# controller-r3.net
KiCad netlist of a schematic drawn in EAGLE
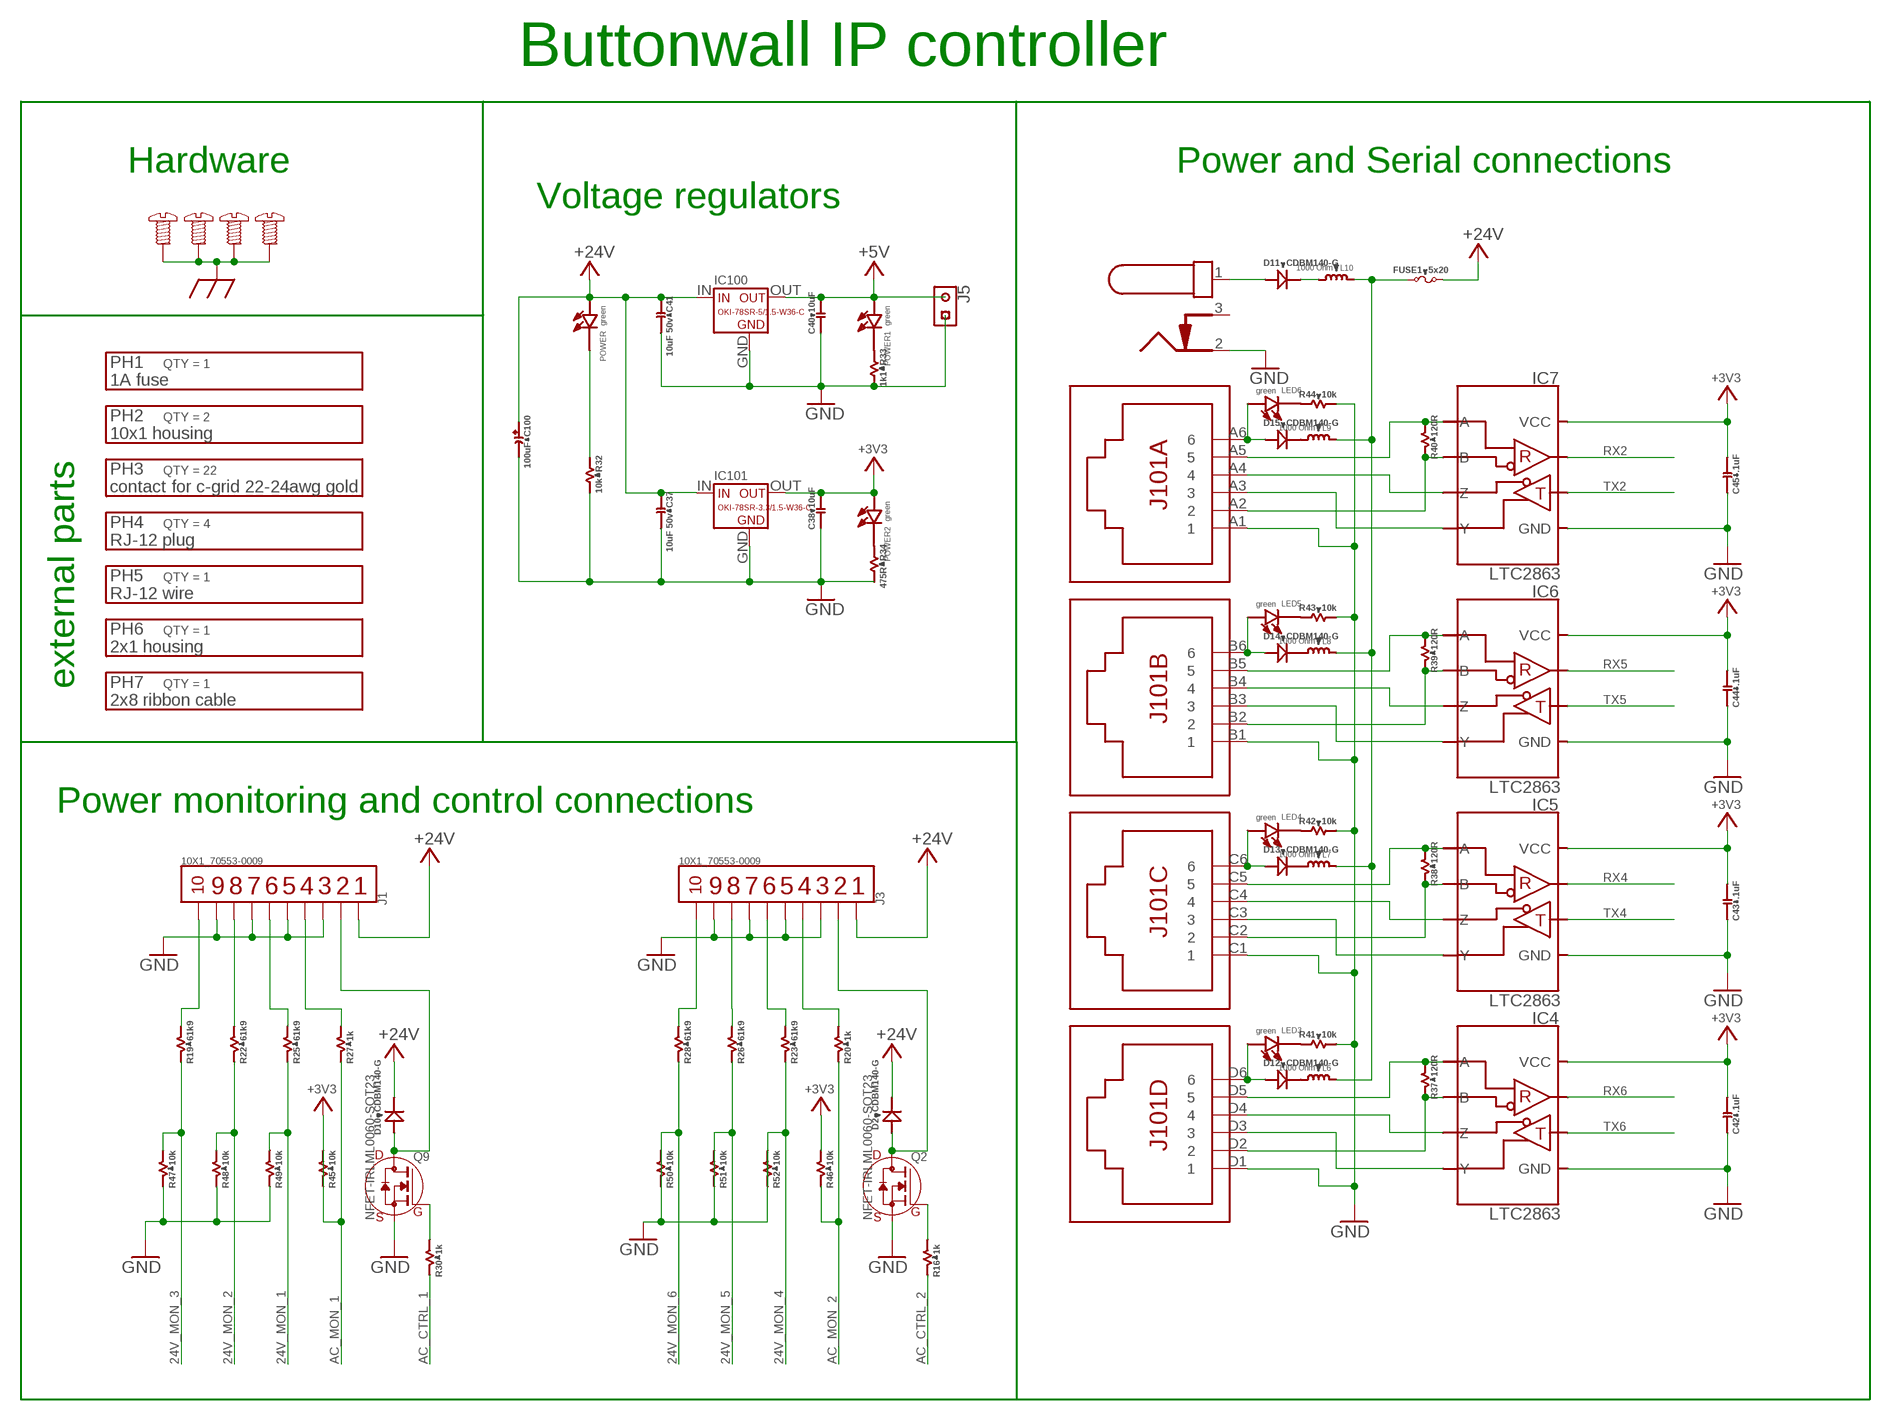
[diagram p0: schematic, sheet 1]
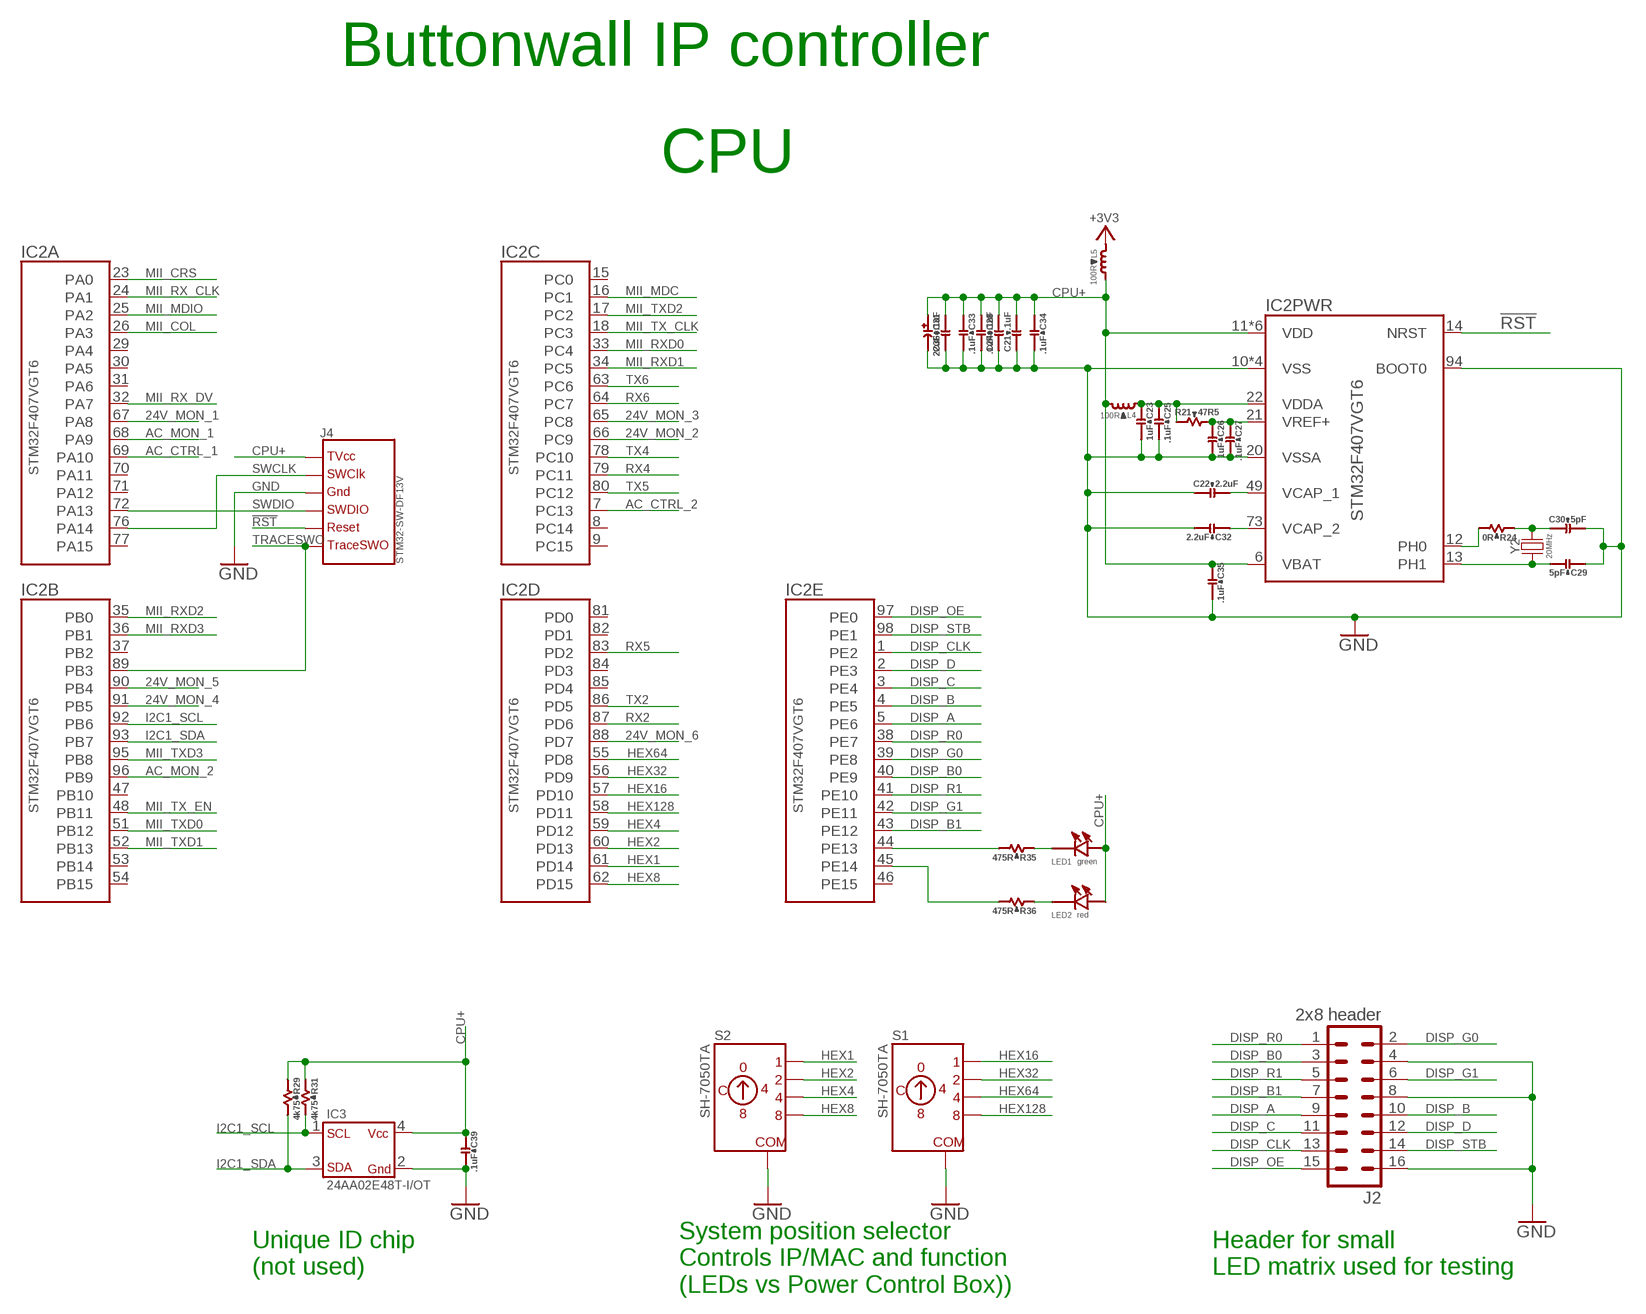
[diagram p1: schematic, sheet 2]
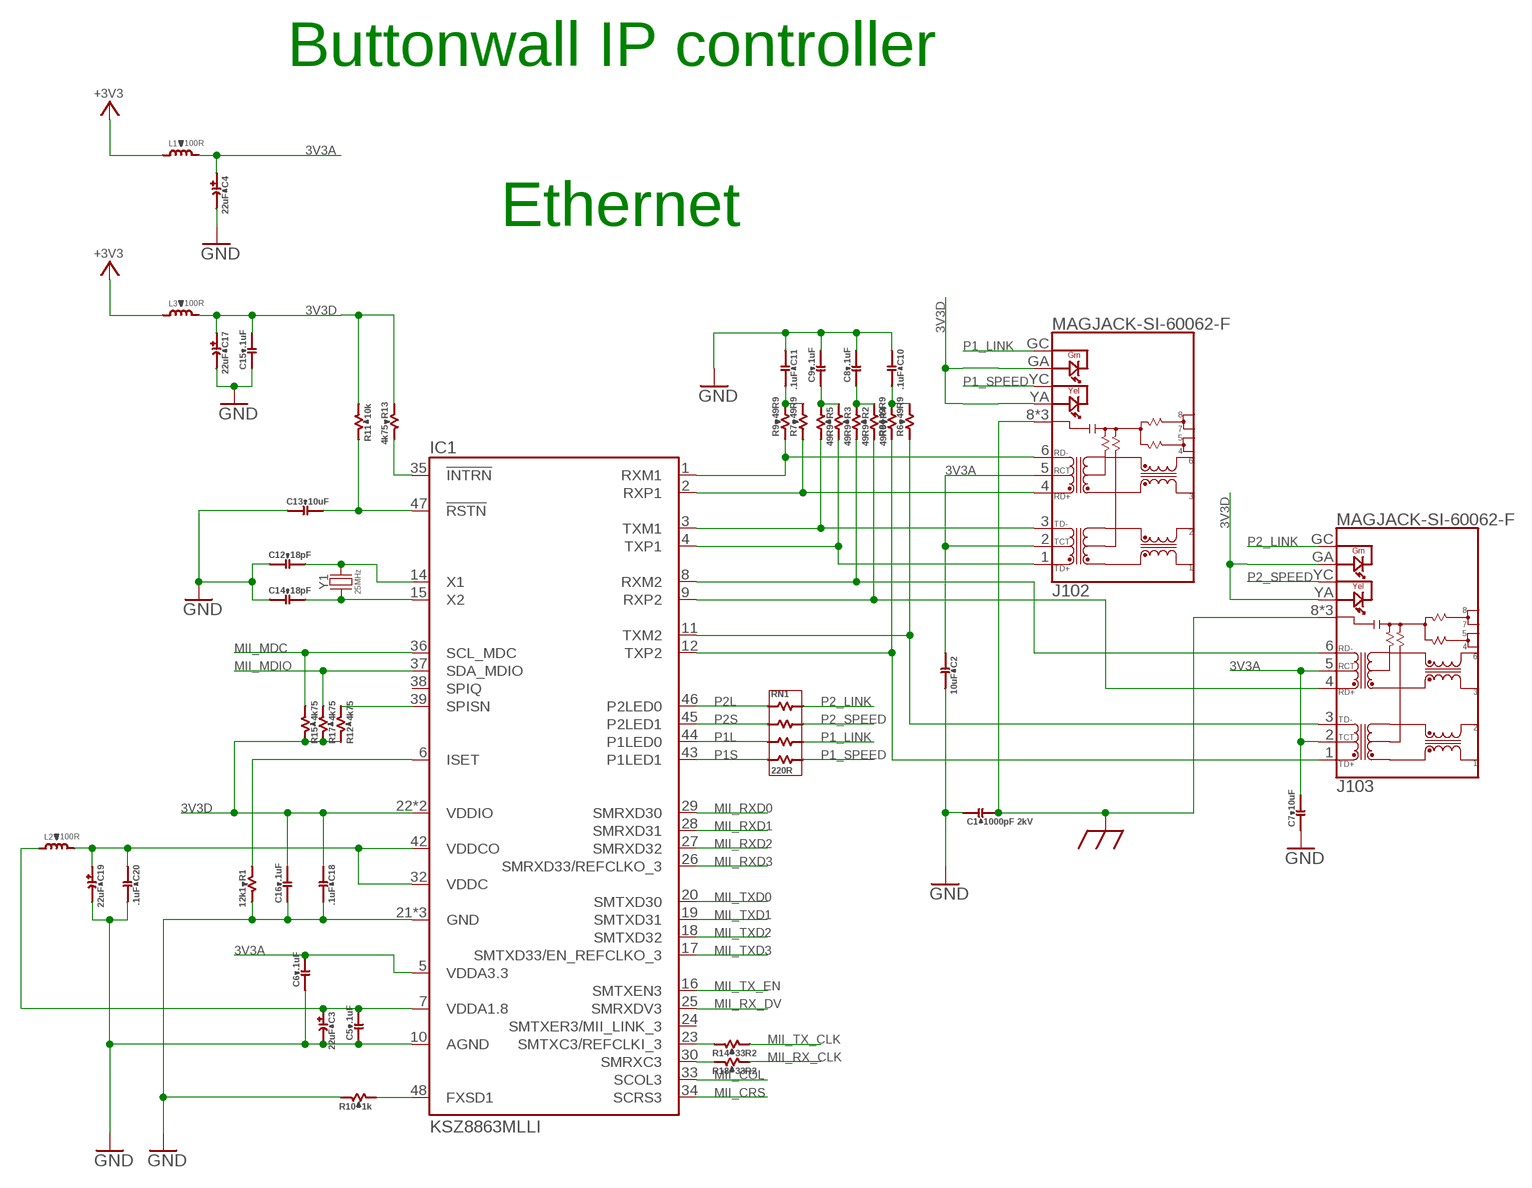
[diagram p2: schematic, sheet 3]

(export (version "E")
  (design (tool "Eeschema 10.0.6"))
  (components
    (comp (ref "C21")
      (value ".1uF")
      (footprint "eagle-import:C0603B")
      (fields (field (name "PARTNO") "CGA3E2X7R1H104K080AA"))
      (libsource (lib "eagle-import") (part "C0603"))
    )
    (comp (ref "C22")
      (value "2.2uF")
      (footprint "eagle-import:C0603B")
      (fields (field (name "PARTNO") "C1608X5R1V225K080AC"))
      (libsource (lib "eagle-import") (part "C0603"))
    )
    (comp (ref "C23")
      (value "1uF")
      (footprint "eagle-import:C0603B")
      (fields (field (name "PARTNO") "CGA3E3X5R1H105K080AB"))
      (libsource (lib "eagle-import") (part "C0603"))
    )
    (comp (ref "C24")
      (value ".1uF")
      (footprint "eagle-import:C0603B")
      (fields (field (name "PARTNO") "CGA3E2X7R1H104K080AA"))
      (libsource (lib "eagle-import") (part "C0603"))
    )
    (comp (ref "C25")
      (value ".1uF")
      (footprint "eagle-import:C0603B")
      (fields (field (name "PARTNO") "CGA3E2X7R1H104K080AA"))
      (libsource (lib "eagle-import") (part "C0603"))
    )
    (comp (ref "C26")
      (value "1uF")
      (footprint "eagle-import:C0603B")
      (fields (field (name "PARTNO") "CGA3E3X5R1H105K080AB"))
      (libsource (lib "eagle-import") (part "C0603"))
    )
    (comp (ref "C27")
      (value ".1uF")
      (footprint "eagle-import:C0603B")
      (fields (field (name "PARTNO") "CGA3E2X7R1H104K080AA"))
      (libsource (lib "eagle-import") (part "C0603"))
    )
    (comp (ref "C28")
      (value ".1uF")
      (footprint "eagle-import:C0603B")
      (fields (field (name "PARTNO") "CGA3E2X7R1H104K080AA"))
      (libsource (lib "eagle-import") (part "C0603"))
    )
    (comp (ref "C29")
      (value "5pF")
      (footprint "eagle-import:C0603B")
      (fields (field (name "PARTNO") "CGA3E2C0G1H050C080AA"))
      (libsource (lib "eagle-import") (part "C0603"))
    )
    (comp (ref "C30")
      (value "5pF")
      (footprint "eagle-import:C0603B")
      (fields (field (name "PARTNO") "CGA3E2C0G1H050C080AA"))
      (libsource (lib "eagle-import") (part "C0603"))
    )
    (comp (ref "C31")
      (value "22uF")
      (footprint "eagle-import:B_3528-21R")
      (fields (field (name "PARTNO") "293D226X96R3B2TE3"))
      (libsource (lib "eagle-import") (part "CPOL-B/3528"))
    )
    (comp (ref "C32")
      (value "2.2uF")
      (footprint "eagle-import:C0603B")
      (fields (field (name "PARTNO") "C1608X5R1V225K080AC"))
      (libsource (lib "eagle-import") (part "C0603"))
    )
    (comp (ref "C33")
      (value ".1uF")
      (footprint "eagle-import:C0603B")
      (fields (field (name "PARTNO") "CGA3E2X7R1H104K080AA"))
      (libsource (lib "eagle-import") (part "C0603"))
    )
    (comp (ref "C34")
      (value ".1uF")
      (footprint "eagle-import:C0603B")
      (fields (field (name "PARTNO") "CGA3E2X7R1H104K080AA"))
      (libsource (lib "eagle-import") (part "C0603"))
    )
    (comp (ref "C35")
      (value ".1uF")
      (footprint "eagle-import:C0603B")
      (fields (field (name "PARTNO") "CGA3E2X7R1H104K080AA"))
      (libsource (lib "eagle-import") (part "C0603"))
    )
    (comp (ref "C36")
      (value ".1uF")
      (footprint "eagle-import:C0603B")
      (fields (field (name "PARTNO") "CGA3E2X7R1H104K080AA"))
      (libsource (lib "eagle-import") (part "C0603"))
    )
    (comp (ref "C39")
      (value ".1uF")
      (footprint "eagle-import:C0603B")
      (fields (field (name "PARTNO") "CGA3E2X7R1H104K080AA"))
      (libsource (lib "eagle-import") (part "C0603"))
    )
    (comp (ref "IC2")
      (value "STM32F407VGT6")
      (footprint "eagle-import:LQFP-100")
      (fields (field (name "PARTNO") "STM32F407VGT6"))
      (libsource (lib "eagle-import") (part "STM32F40V_T7"))
    )
    (comp (ref "IC3")
      (value "24AA02E48T-I/OT")
      (footprint "eagle-import:SOT-23-5")
      (libsource (lib "eagle-import") (part "24AA02E48T-I/OT"))
    )
    (comp (ref "J2")
      (value "2x8 header")
      (footprint "eagle-import:ML16")
      (fields (field (name "PARTNO") "SBH11-PBPC-D08-ST-BK"))
      (libsource (lib "eagle-import") (part "ML16"))
    )
    (comp (ref "J4")
      (value "STM32-SW-DF13V")
      (footprint "eagle-import:DF13-6P-1.25V")
      (fields (field (name "PARTNO") "DF13C-6P-1.25V(20)"))
      (libsource (lib "eagle-import") (part "STM32-SW-DF13V"))
    )
    (comp (ref "L4")
      (value "100R")
      (footprint "eagle-import:R0603B")
      (fields (field (name "PARTNO") "MPZ1608S101A"))
      (libsource (lib "eagle-import") (part "L0603"))
    )
    (comp (ref "L5")
      (value "100R")
      (footprint "eagle-import:R0603B")
      (fields (field (name "PARTNO") "MPZ1608S101A"))
      (libsource (lib "eagle-import") (part "L0603"))
    )
    (comp (ref "LED1")
      (value "green")
      (footprint "eagle-import:CHIPLED_0603")
      (fields (field (name "PARTNO") "LTST-C190KGKT"))
      (libsource (lib "eagle-import") (part "LED0603"))
    )
    (comp (ref "LED2")
      (value "red")
      (footprint "eagle-import:CHIPLED_0603")
      (fields (field (name "PARTNO") "LTST-C190KRKT"))
      (libsource (lib "eagle-import") (part "LED0603"))
    )
    (comp (ref "R21")
      (value "47R5")
      (footprint "eagle-import:R0603B")
      (fields (field (name "PARTNO") "CRCW060347R5FKEA"))
      (libsource (lib "eagle-import") (part "R0603"))
    )
    (comp (ref "R24")
      (value "0R")
      (footprint "eagle-import:R0603B")
      (fields (field (name "PARTNO") "CRCW06030000Z0EA"))
      (libsource (lib "eagle-import") (part "R0603"))
    )
    (comp (ref "R29")
      (value "4k75")
      (footprint "eagle-import:R0603B")
      (fields (field (name "PARTNO") "CRCW06034K75FKEA"))
      (libsource (lib "eagle-import") (part "R0603"))
    )
    (comp (ref "R31")
      (value "4k75")
      (footprint "eagle-import:R0603B")
      (fields (field (name "PARTNO") "CRCW06034K75FKEA"))
      (libsource (lib "eagle-import") (part "R0603"))
    )
    (comp (ref "R35")
      (value "475R")
      (footprint "eagle-import:R0603B")
      (fields (field (name "PARTNO") "CRCW0603475RFKEA"))
      (libsource (lib "eagle-import") (part "R0603"))
    )
    (comp (ref "R36")
      (value "475R")
      (footprint "eagle-import:R0603B")
      (fields (field (name "PARTNO") "CRCW0603475RFKEA"))
      (libsource (lib "eagle-import") (part "R0603"))
    )
    (comp (ref "S1")
      (value "SH-7050TA")
      (footprint "eagle-import:SH-7050TA")
      (libsource (lib "eagle-import") (part "HEXROTARY"))
    )
    (comp (ref "S2")
      (value "SH-7050TA")
      (footprint "eagle-import:SH-7050TA")
      (libsource (lib "eagle-import") (part "HEXROTARY"))
    )
    (comp (ref "Y2")
      (value "20MHz")
      (footprint "eagle-import:5X3.2")
      (fields (field (name "PARTNO") "7A-20.000MAHE-T"))
      (libsource (lib "eagle-import") (part "XTAL-2_5X3.2"))
    )
    (comp (ref "C37")
      (value "10uF 50v")
      (footprint "eagle-import:C1206B")
      (fields (field (name "PARTNO") "CL31A106KBHNNNE"))
      (libsource (lib "eagle-import") (part "C1206"))
    )
    (comp (ref "C38")
      (value "10uF")
      (footprint "eagle-import:C0603B")
      (fields (field (name "PARTNO") "C1608X6S1A106M080AC"))
      (libsource (lib "eagle-import") (part "C0603"))
    )
    (comp (ref "C40")
      (value "10uF")
      (footprint "eagle-import:C0603B")
      (fields (field (name "PARTNO") "C1608X6S1A106M080AC"))
      (libsource (lib "eagle-import") (part "C0603"))
    )
    (comp (ref "C41")
      (value "10uF 50v")
      (footprint "eagle-import:C1206B")
      (fields (field (name "PARTNO") "CL31A106KBHNNNE"))
      (libsource (lib "eagle-import") (part "C1206"))
    )
    (comp (ref "C42")
      (value ".1uF")
      (footprint "eagle-import:C0603B")
      (fields (field (name "PARTNO") "CGA3E2X7R1H104K080AA"))
      (libsource (lib "eagle-import") (part "C0603"))
    )
    (comp (ref "C43")
      (value ".1uF")
      (footprint "eagle-import:C0603B")
      (fields (field (name "PARTNO") "CGA3E2X7R1H104K080AA"))
      (libsource (lib "eagle-import") (part "C0603"))
    )
    (comp (ref "C44")
      (value ".1uF")
      (footprint "eagle-import:C0603B")
      (fields (field (name "PARTNO") "CGA3E2X7R1H104K080AA"))
      (libsource (lib "eagle-import") (part "C0603"))
    )
    (comp (ref "C45")
      (value ".1uF")
      (footprint "eagle-import:C0603B")
      (fields (field (name "PARTNO") "CGA3E2X7R1H104K080AA"))
      (libsource (lib "eagle-import") (part "C0603"))
    )
    (comp (ref "C100")
      (value "100uF")
      (footprint "eagle-import:E3,5-8")
      (fields (field (name "PARTNO") "EEU-FM1H101"))
      (libsource (lib "eagle-import") (part "CPOL-TH-3.5-8"))
    )
    (comp (ref "D2")
      (value "CDBM140-G")
      (footprint "eagle-import:SOD-123")
      (libsource (lib "eagle-import") (part "D_SOD123"))
    )
    (comp (ref "D10")
      (value "CDBM140-G")
      (footprint "eagle-import:SOD-123")
      (libsource (lib "eagle-import") (part "D_SOD123"))
    )
    (comp (ref "D11")
      (value "CDBM140-G")
      (footprint "eagle-import:SOD-123")
      (libsource (lib "eagle-import") (part "D_SOD123"))
    )
    (comp (ref "D12")
      (value "CDBM140-G")
      (footprint "eagle-import:SOD-123")
      (libsource (lib "eagle-import") (part "D_SOD123"))
    )
    (comp (ref "D13")
      (value "CDBM140-G")
      (footprint "eagle-import:SOD-123")
      (libsource (lib "eagle-import") (part "D_SOD123"))
    )
    (comp (ref "D14")
      (value "CDBM140-G")
      (footprint "eagle-import:SOD-123")
      (libsource (lib "eagle-import") (part "D_SOD123"))
    )
    (comp (ref "D15")
      (value "CDBM140-G")
      (footprint "eagle-import:SOD-123")
      (libsource (lib "eagle-import") (part "D_SOD123"))
    )
    (comp (ref "FUSE1")
      (value "5x20")
      (footprint "eagle-import:649")
      (fields (field (name "PARTNO") "64900001039"))
      (libsource (lib "eagle-import") (part "F-649"))
    )
    (comp (ref "IC4")
      (value "LTC2863")
      (footprint "eagle-import:SO08")
      (fields (field (name "PARTNO") "LTC2863IS8-1#PBF"))
      (libsource (lib "eagle-import") (part "LTC2863"))
    )
    (comp (ref "IC5")
      (value "LTC2863")
      (footprint "eagle-import:SO08")
      (fields (field (name "PARTNO") "LTC2863IS8-1#PBF"))
      (libsource (lib "eagle-import") (part "LTC2863"))
    )
    (comp (ref "IC6")
      (value "LTC2863")
      (footprint "eagle-import:SO08")
      (fields (field (name "PARTNO") "LTC2863IS8-1#PBF"))
      (libsource (lib "eagle-import") (part "LTC2863"))
    )
    (comp (ref "IC7")
      (value "LTC2863")
      (footprint "eagle-import:SO08")
      (fields (field (name "PARTNO") "LTC2863IS8-1#PBF"))
      (libsource (lib "eagle-import") (part "LTC2863"))
    )
    (comp (ref "IC100")
      (value "OKI-78SR-5/1.5-W36-C")
      (footprint "eagle-import:OKI-78SR-V")
      (libsource (lib "eagle-import") (part "OKI-78SR--W36-C5/1.5"))
    )
    (comp (ref "IC101")
      (value "OKI-78SR-3.3/1.5-W36-C")
      (footprint "eagle-import:OKI-78SR-V")
      (libsource (lib "eagle-import") (part "OKI-78SR--W36-C3.3/1.5"))
    )
    (comp (ref "J1")
      (value "10X1_70553-0009")
      (footprint "eagle-import:MOLEX_70553-(10)")
      (fields (field (name "PARTNO") "0705530009"))
      (libsource (lib "eagle-import") (part "10X1_70553-0009"))
    )
    (comp (ref "J3")
      (value "10X1_70553-0009")
      (footprint "eagle-import:MOLEX_70553-(10)")
      (fields (field (name "PARTNO") "0705530009"))
      (libsource (lib "eagle-import") (part "10X1_70553-0009"))
    )
    (comp (ref "J5")
      (value "1X2_70543")
      (footprint "eagle-import:MOLEX_70543-0001")
      (fields (field (name "PARTNO") "0705430001"))
      (libsource (lib "eagle-import") (part "1X2_70543"))
    )
    (comp (ref "J100")
      (value "PJ-102AH")
      (footprint "eagle-import:PJ-102(DC_JACK)")
      (libsource (lib "eagle-import") (part "DC_JACK"))
    )
    (comp (ref "J101")
      (value "RJ12-QUAD")
      (footprint "eagle-import:SS-666604-NF")
      (fields (field (name "PARTNO") "SS-666604-NF"))
      (libsource (lib "eagle-import") (part "RJ12-QUAD"))
    )
    (comp (ref "L6")
      (value "1000 Ohm")
      (footprint "eagle-import:R0603B")
      (fields (field (name "PARTNO") "MMZ1608R102A"))
      (libsource (lib "eagle-import") (part "L0603"))
    )
    (comp (ref "L7")
      (value "1000 Ohm")
      (footprint "eagle-import:R0603B")
      (fields (field (name "PARTNO") "MMZ1608R102A"))
      (libsource (lib "eagle-import") (part "L0603"))
    )
    (comp (ref "L8")
      (value "1000 Ohm")
      (footprint "eagle-import:R0603B")
      (fields (field (name "PARTNO") "MMZ1608R102A"))
      (libsource (lib "eagle-import") (part "L0603"))
    )
    (comp (ref "L9")
      (value "1000 Ohm")
      (footprint "eagle-import:R0603B")
      (fields (field (name "PARTNO") "MMZ1608R102A"))
      (libsource (lib "eagle-import") (part "L0603"))
    )
    (comp (ref "L10")
      (value "1000 Ohm")
      (footprint "eagle-import:R0603B")
      (fields (field (name "PARTNO") "MMZ1608R102A"))
      (libsource (lib "eagle-import") (part "L0603"))
    )
    (comp (ref "LED3")
      (value "green")
      (footprint "eagle-import:CHIPLED_0603")
      (fields (field (name "PARTNO") "LTST-C190KGKT"))
      (libsource (lib "eagle-import") (part "LED0603"))
    )
    (comp (ref "LED4")
      (value "green")
      (footprint "eagle-import:CHIPLED_0603")
      (fields (field (name "PARTNO") "LTST-C190KGKT"))
      (libsource (lib "eagle-import") (part "LED0603"))
    )
    (comp (ref "LED5")
      (value "green")
      (footprint "eagle-import:CHIPLED_0603")
      (fields (field (name "PARTNO") "LTST-C190KGKT"))
      (libsource (lib "eagle-import") (part "LED0603"))
    )
    (comp (ref "LED6")
      (value "green")
      (footprint "eagle-import:CHIPLED_0603")
      (fields (field (name "PARTNO") "LTST-C190KGKT"))
      (libsource (lib "eagle-import") (part "LED0603"))
    )
    (comp (ref "POWER")
      (value "green")
      (footprint "eagle-import:CHIPLED_0603")
      (fields (field (name "PARTNO") "LTST-C190KGKT"))
      (libsource (lib "eagle-import") (part "LED0603"))
    )
    (comp (ref "POWER1")
      (value "green")
      (footprint "eagle-import:CHIPLED_0603")
      (fields (field (name "PARTNO") "LTST-C190KGKT"))
      (libsource (lib "eagle-import") (part "LED0603"))
    )
    (comp (ref "POWER2")
      (value "green")
      (footprint "eagle-import:CHIPLED_0603")
      (fields (field (name "PARTNO") "LTST-C190KGKT"))
      (libsource (lib "eagle-import") (part "LED0603"))
    )
    (comp (ref "Q2")
      (value "NFET-IRLML0060-SOT23")
      (footprint "eagle-import:SOT-23")
      (fields (field (name "PARTNO") "IRLML0060TRPBF"))
      (libsource (lib "eagle-import") (part "NFET--SOT23IRLML0060"))
    )
    (comp (ref "Q9")
      (value "NFET-IRLML0060-SOT23")
      (footprint "eagle-import:SOT-23")
      (fields (field (name "PARTNO") "IRLML0060TRPBF"))
      (libsource (lib "eagle-import") (part "NFET--SOT23IRLML0060"))
    )
    (comp (ref "R16")
      (value "1k")
      (footprint "eagle-import:R0603B")
      (fields (field (name "PARTNO") "CRCW06031K00FKEA"))
      (libsource (lib "eagle-import") (part "R0603"))
    )
    (comp (ref "R19")
      (value "61k9")
      (footprint "eagle-import:R0603B")
      (fields (field (name "PARTNO") "CRCW060361K9FKEA"))
      (libsource (lib "eagle-import") (part "R0603"))
    )
    (comp (ref "R20")
      (value "1k")
      (footprint "eagle-import:R0603B")
      (fields (field (name "PARTNO") "CRCW06031K00FKEA"))
      (libsource (lib "eagle-import") (part "R0603"))
    )
    (comp (ref "R22")
      (value "61k9")
      (footprint "eagle-import:R0603B")
      (fields (field (name "PARTNO") "CRCW060361K9FKEA"))
      (libsource (lib "eagle-import") (part "R0603"))
    )
    (comp (ref "R23")
      (value "61k9")
      (footprint "eagle-import:R0603B")
      (fields (field (name "PARTNO") "CRCW060361K9FKEA"))
      (libsource (lib "eagle-import") (part "R0603"))
    )
    (comp (ref "R25")
      (value "61k9")
      (footprint "eagle-import:R0603B")
      (fields (field (name "PARTNO") "CRCW060361K9FKEA"))
      (libsource (lib "eagle-import") (part "R0603"))
    )
    (comp (ref "R26")
      (value "61k9")
      (footprint "eagle-import:R0603B")
      (fields (field (name "PARTNO") "CRCW060361K9FKEA"))
      (libsource (lib "eagle-import") (part "R0603"))
    )
    (comp (ref "R27")
      (value "1k")
      (footprint "eagle-import:R0603B")
      (fields (field (name "PARTNO") "CRCW06031K00FKEA"))
      (libsource (lib "eagle-import") (part "R0603"))
    )
    (comp (ref "R28")
      (value "61k9")
      (footprint "eagle-import:R0603B")
      (fields (field (name "PARTNO") "CRCW060361K9FKEA"))
      (libsource (lib "eagle-import") (part "R0603"))
    )
    (comp (ref "R30")
      (value "1k")
      (footprint "eagle-import:R0603B")
      (fields (field (name "PARTNO") "CRCW06031K00FKEA"))
      (libsource (lib "eagle-import") (part "R0603"))
    )
    (comp (ref "R32")
      (value "10k")
      (footprint "eagle-import:R0603B")
      (fields (field (name "PARTNO") "CRCW060310K0FKEA"))
      (libsource (lib "eagle-import") (part "R0603"))
    )
    (comp (ref "R33")
      (value "1k1")
      (footprint "eagle-import:R0603B")
      (fields (field (name "PARTNO") "CRCW06031K10FKEA"))
      (libsource (lib "eagle-import") (part "R0603"))
    )
    (comp (ref "R34")
      (value "475R")
      (footprint "eagle-import:R0603B")
      (fields (field (name "PARTNO") "CRCW0603475RFKEA"))
      (libsource (lib "eagle-import") (part "R0603"))
    )
    (comp (ref "R37")
      (value "120R")
      (footprint "eagle-import:R1206B")
      (fields (field (name "PARTNO") "CRCW1206120RFKEA"))
      (libsource (lib "eagle-import") (part "R1206"))
    )
    (comp (ref "R38")
      (value "120R")
      (footprint "eagle-import:R1206B")
      (fields (field (name "PARTNO") "CRCW1206120RFKEA"))
      (libsource (lib "eagle-import") (part "R1206"))
    )
    (comp (ref "R39")
      (value "120R")
      (footprint "eagle-import:R1206B")
      (fields (field (name "PARTNO") "CRCW1206120RFKEA"))
      (libsource (lib "eagle-import") (part "R1206"))
    )
    (comp (ref "R40")
      (value "120R")
      (footprint "eagle-import:R1206B")
      (fields (field (name "PARTNO") "CRCW1206120RFKEA"))
      (libsource (lib "eagle-import") (part "R1206"))
    )
    (comp (ref "R41")
      (value "10k")
      (footprint "eagle-import:R0603B")
      (fields (field (name "PARTNO") "CRCW060310K0FKEA"))
      (libsource (lib "eagle-import") (part "R0603"))
    )
    (comp (ref "R42")
      (value "10k")
      (footprint "eagle-import:R0603B")
      (fields (field (name "PARTNO") "CRCW060310K0FKEA"))
      (libsource (lib "eagle-import") (part "R0603"))
    )
    (comp (ref "R43")
      (value "10k")
      (footprint "eagle-import:R0603B")
      (fields (field (name "PARTNO") "CRCW060310K0FKEA"))
      (libsource (lib "eagle-import") (part "R0603"))
    )
    (comp (ref "R44")
      (value "10k")
      (footprint "eagle-import:R0603B")
      (fields (field (name "PARTNO") "CRCW060310K0FKEA"))
      (libsource (lib "eagle-import") (part "R0603"))
    )
    (comp (ref "R45")
      (value "10k")
      (footprint "eagle-import:R0603B")
      (fields (field (name "PARTNO") "CRCW060310K0FKEA"))
      (libsource (lib "eagle-import") (part "R0603"))
    )
    (comp (ref "R46")
      (value "10k")
      (footprint "eagle-import:R0603B")
      (fields (field (name "PARTNO") "CRCW060310K0FKEA"))
      (libsource (lib "eagle-import") (part "R0603"))
    )
    (comp (ref "R47")
      (value "10k")
      (footprint "eagle-import:R0603B")
      (fields (field (name "PARTNO") "CRCW060310K0FKEA"))
      (libsource (lib "eagle-import") (part "R0603"))
    )
    (comp (ref "R48")
      (value "10k")
      (footprint "eagle-import:R0603B")
      (fields (field (name "PARTNO") "CRCW060310K0FKEA"))
      (libsource (lib "eagle-import") (part "R0603"))
    )
    (comp (ref "R49")
      (value "10k")
      (footprint "eagle-import:R0603B")
      (fields (field (name "PARTNO") "CRCW060310K0FKEA"))
      (libsource (lib "eagle-import") (part "R0603"))
    )
    (comp (ref "R50")
      (value "10k")
      (footprint "eagle-import:R0603B")
      (fields (field (name "PARTNO") "CRCW060310K0FKEA"))
      (libsource (lib "eagle-import") (part "R0603"))
    )
    (comp (ref "R51")
      (value "10k")
      (footprint "eagle-import:R0603B")
      (fields (field (name "PARTNO") "CRCW060310K0FKEA"))
      (libsource (lib "eagle-import") (part "R0603"))
    )
    (comp (ref "R52")
      (value "10k")
      (footprint "eagle-import:R0603B")
      (fields (field (name "PARTNO") "CRCW060310K0FKEA"))
      (libsource (lib "eagle-import") (part "R0603"))
    )
    (comp (ref "SCREW1")
      (value "SCREW-632-0-PSHP")
      (footprint "eagle-import:SMTPR-6-1")
      (libsource (lib "eagle-import") (part "SCREW--PSHP632-0"))
    )
    (comp (ref "SCREW2")
      (value "SCREW-632-0-PSHP")
      (footprint "eagle-import:SMTPR-6-1")
      (libsource (lib "eagle-import") (part "SCREW--PSHP632-0"))
    )
    (comp (ref "SCREW3")
      (value "SCREW-632-0-PSHP")
      (footprint "eagle-import:SMTPR-6-1")
      (libsource (lib "eagle-import") (part "SCREW--PSHP632-0"))
    )
    (comp (ref "SCREW4")
      (value "SCREW-632-0-PSHP")
      (footprint "eagle-import:SMTPR-6-1")
      (libsource (lib "eagle-import") (part "SCREW--PSHP632-0"))
    )
    (comp (ref "C1")
      (value "1000pF 2kV")
      (footprint "eagle-import:C1206B")
      (fields (field (name "PARTNO") "202R18W102KV4E"))
      (libsource (lib "eagle-import") (part "C1206"))
    )
    (comp (ref "C2")
      (value "10uF")
      (footprint "eagle-import:C0603B")
      (fields (field (name "PARTNO") "C1608X6S1A106M080AC"))
      (libsource (lib "eagle-import") (part "C0603"))
    )
    (comp (ref "C3")
      (value "22uF")
      (footprint "eagle-import:B_3528-21R")
      (fields (field (name "PARTNO") "293D226X96R3B2TE3"))
      (libsource (lib "eagle-import") (part "CPOL-B/3528"))
    )
    (comp (ref "C4")
      (value "22uF")
      (footprint "eagle-import:B_3528-21R")
      (fields (field (name "PARTNO") "293D226X96R3B2TE3"))
      (libsource (lib "eagle-import") (part "CPOL-B/3528"))
    )
    (comp (ref "C5")
      (value ".1uF")
      (footprint "eagle-import:C0603B")
      (fields (field (name "PARTNO") "CGA3E2X7R1H104K080AA"))
      (libsource (lib "eagle-import") (part "C0603"))
    )
    (comp (ref "C6")
      (value ".1uF")
      (footprint "eagle-import:C0603B")
      (fields (field (name "PARTNO") "CGA3E2X7R1H104K080AA"))
      (libsource (lib "eagle-import") (part "C0603"))
    )
    (comp (ref "C7")
      (value "10uF")
      (footprint "eagle-import:C0603B")
      (fields (field (name "PARTNO") "C1608X6S1A106M080AC"))
      (libsource (lib "eagle-import") (part "C0603"))
    )
    (comp (ref "C8")
      (value ".1uF")
      (footprint "eagle-import:C0603B")
      (fields (field (name "PARTNO") "CGA3E2X7R1H104K080AA"))
      (libsource (lib "eagle-import") (part "C0603"))
    )
    (comp (ref "C9")
      (value ".1uF")
      (footprint "eagle-import:C0603B")
      (fields (field (name "PARTNO") "CGA3E2X7R1H104K080AA"))
      (libsource (lib "eagle-import") (part "C0603"))
    )
    (comp (ref "C10")
      (value ".1uF")
      (footprint "eagle-import:C0603B")
      (fields (field (name "PARTNO") "CGA3E2X7R1H104K080AA"))
      (libsource (lib "eagle-import") (part "C0603"))
    )
    (comp (ref "C11")
      (value ".1uF")
      (footprint "eagle-import:C0603B")
      (fields (field (name "PARTNO") "CGA3E2X7R1H104K080AA"))
      (libsource (lib "eagle-import") (part "C0603"))
    )
    (comp (ref "C12")
      (value "18pF")
      (footprint "eagle-import:C0603B")
      (fields (field (name "PARTNO") "CGA3E2C0G1H180J080AA"))
      (libsource (lib "eagle-import") (part "C0603"))
    )
    (comp (ref "C13")
      (value "10uF")
      (footprint "eagle-import:C0603B")
      (fields (field (name "PARTNO") "C1608X6S1A106M080AC"))
      (libsource (lib "eagle-import") (part "C0603"))
    )
    (comp (ref "C14")
      (value "18pF")
      (footprint "eagle-import:C0603B")
      (fields (field (name "PARTNO") "CGA3E2C0G1H180J080AA"))
      (libsource (lib "eagle-import") (part "C0603"))
    )
    (comp (ref "C15")
      (value ".1uF")
      (footprint "eagle-import:C0603B")
      (fields (field (name "PARTNO") "CGA3E2X7R1H104K080AA"))
      (libsource (lib "eagle-import") (part "C0603"))
    )
    (comp (ref "C16")
      (value ".1uF")
      (footprint "eagle-import:C0603B")
      (fields (field (name "PARTNO") "CGA3E2X7R1H104K080AA"))
      (libsource (lib "eagle-import") (part "C0603"))
    )
    (comp (ref "C17")
      (value "22uF")
      (footprint "eagle-import:B_3528-21R")
      (fields (field (name "PARTNO") "293D226X96R3B2TE3"))
      (libsource (lib "eagle-import") (part "CPOL-B/3528"))
    )
    (comp (ref "C18")
      (value ".1uF")
      (footprint "eagle-import:C0603B")
      (fields (field (name "PARTNO") "CGA3E2X7R1H104K080AA"))
      (libsource (lib "eagle-import") (part "C0603"))
    )
    (comp (ref "C19")
      (value "22uF")
      (footprint "eagle-import:B_3528-21R")
      (fields (field (name "PARTNO") "293D226X96R3B2TE3"))
      (libsource (lib "eagle-import") (part "CPOL-B/3528"))
    )
    (comp (ref "C20")
      (value ".1uF")
      (footprint "eagle-import:C0603B")
      (fields (field (name "PARTNO") "CGA3E2X7R1H104K080AA"))
      (libsource (lib "eagle-import") (part "C0603"))
    )
    (comp (ref "IC1")
      (value "KSZ8863MLLI")
      (footprint "eagle-import:TQFP48")
      (libsource (lib "eagle-import") (part "KSZ8863MLLI"))
    )
    (comp (ref "J102")
      (value "MAGJACK-SI-60062-F")
      (footprint "eagle-import:SI-60062-F")
      (fields (field (name "PARTNO") "SI-60062-F"))
      (libsource (lib "eagle-import") (part "MAGJACK-SI-60062-F"))
    )
    (comp (ref "J103")
      (value "MAGJACK-SI-60062-F")
      (footprint "eagle-import:SI-60062-F")
      (fields (field (name "PARTNO") "SI-60062-F"))
      (libsource (lib "eagle-import") (part "MAGJACK-SI-60062-F"))
    )
    (comp (ref "L1")
      (value "100R")
      (footprint "eagle-import:R0603B")
      (fields (field (name "PARTNO") "MPZ1608S101A"))
      (libsource (lib "eagle-import") (part "L0603"))
    )
    (comp (ref "L2")
      (value "100R")
      (footprint "eagle-import:R0603B")
      (fields (field (name "PARTNO") "MPZ1608S101A"))
      (libsource (lib "eagle-import") (part "L0603"))
    )
    (comp (ref "L3")
      (value "100R")
      (footprint "eagle-import:R0603B")
      (fields (field (name "PARTNO") "MPZ1608S101A"))
      (libsource (lib "eagle-import") (part "L0603"))
    )
    (comp (ref "R1")
      (value "12k1")
      (footprint "eagle-import:R0603B")
      (fields (field (name "PARTNO") "CRCW060312K1FKEA"))
      (libsource (lib "eagle-import") (part "R0603"))
    )
    (comp (ref "R2")
      (value "49R9")
      (footprint "eagle-import:R0603B")
      (fields (field (name "PARTNO") "CRCW060349R9FKEA"))
      (libsource (lib "eagle-import") (part "R0603"))
    )
    (comp (ref "R3")
      (value "49R9")
      (footprint "eagle-import:R0603B")
      (fields (field (name "PARTNO") "CRCW060349R9FKEA"))
      (libsource (lib "eagle-import") (part "R0603"))
    )
    (comp (ref "R4")
      (value "49R9")
      (footprint "eagle-import:R0603B")
      (fields (field (name "PARTNO") "CRCW060349R9FKEA"))
      (libsource (lib "eagle-import") (part "R0603"))
    )
    (comp (ref "R5")
      (value "49R9")
      (footprint "eagle-import:R0603B")
      (fields (field (name "PARTNO") "CRCW060349R9FKEA"))
      (libsource (lib "eagle-import") (part "R0603"))
    )
    (comp (ref "R6")
      (value "49R9")
      (footprint "eagle-import:R0603B")
      (fields (field (name "PARTNO") "CRCW060349R9FKEA"))
      (libsource (lib "eagle-import") (part "R0603"))
    )
    (comp (ref "R7")
      (value "49R9")
      (footprint "eagle-import:R0603B")
      (fields (field (name "PARTNO") "CRCW060349R9FKEA"))
      (libsource (lib "eagle-import") (part "R0603"))
    )
    (comp (ref "R8")
      (value "49R9")
      (footprint "eagle-import:R0603B")
      (fields (field (name "PARTNO") "CRCW060349R9FKEA"))
      (libsource (lib "eagle-import") (part "R0603"))
    )
    (comp (ref "R9")
      (value "49R9")
      (footprint "eagle-import:R0603B")
      (fields (field (name "PARTNO") "CRCW060349R9FKEA"))
      (libsource (lib "eagle-import") (part "R0603"))
    )
    (comp (ref "R10")
      (value "1k")
      (footprint "eagle-import:R0603B")
      (fields (field (name "PARTNO") "CRCW06031K00FKEA"))
      (libsource (lib "eagle-import") (part "R0603"))
    )
    (comp (ref "R11")
      (value "10k")
      (footprint "eagle-import:R0603B")
      (fields (field (name "PARTNO") "CRCW060310K0FKEA"))
      (libsource (lib "eagle-import") (part "R0603"))
    )
    (comp (ref "R12")
      (value "4k75")
      (footprint "eagle-import:R0603B")
      (fields (field (name "PARTNO") "CRCW06034K75FKEA"))
      (libsource (lib "eagle-import") (part "R0603"))
    )
    (comp (ref "R13")
      (value "4k75")
      (footprint "eagle-import:R0603B")
      (fields (field (name "PARTNO") "CRCW06034K75FKEA"))
      (libsource (lib "eagle-import") (part "R0603"))
    )
    (comp (ref "R14")
      (value "33R2")
      (footprint "eagle-import:R0603B")
      (fields (field (name "PARTNO") "CRCW060333R2FKEA"))
      (libsource (lib "eagle-import") (part "R0603"))
    )
    (comp (ref "R15")
      (value "4k75")
      (footprint "eagle-import:R0603B")
      (fields (field (name "PARTNO") "CRCW06034K75FKEA"))
      (libsource (lib "eagle-import") (part "R0603"))
    )
    (comp (ref "R17")
      (value "4k75")
      (footprint "eagle-import:R0603B")
      (fields (field (name "PARTNO") "CRCW06034K75FKEA"))
      (libsource (lib "eagle-import") (part "R0603"))
    )
    (comp (ref "R18")
      (value "33R2")
      (footprint "eagle-import:R0603B")
      (fields (field (name "PARTNO") "CRCW060333R2FKEA"))
      (libsource (lib "eagle-import") (part "R0603"))
    )
    (comp (ref "RN1")
      (value "220R")
      (footprint "eagle-import:CTS_742-4")
      (fields (field (name "PARTNO") "742C083221JP"))
      (libsource (lib "eagle-import") (part "R4_742C"))
    )
    (comp (ref "Y1")
      (value "25MHz")
      (footprint "eagle-import:5X3.2")
      (fields (field (name "PARTNO") "7A-25.000MAHE-T"))
      (libsource (lib "eagle-import") (part "XTAL-2_5X3.2"))
    )
  )
  (nets
    (net (code "1") (name "+3V3") (class "Default")
      (node (ref "C38") (pin "2") (pinfunction "P$2_2") (pintype "passive"))
      (node (ref "C42") (pin "2") (pinfunction "P$2_2") (pintype "passive"))
      (node (ref "C43") (pin "2") (pinfunction "P$2_2") (pintype "passive"))
      (node (ref "C44") (pin "2") (pinfunction "P$2_2") (pintype "passive"))
      (node (ref "C45") (pin "2") (pinfunction "P$2_2") (pintype "passive"))
      (node (ref "IC101") (pin "OUT") (pinfunction "OUT_OUT") (pintype "power_in"))
      (node (ref "IC4") (pin "1") (pinfunction "VCC_1") (pintype "power_in"))
      (node (ref "IC5") (pin "1") (pinfunction "VCC_1") (pintype "power_in"))
      (node (ref "IC6") (pin "1") (pinfunction "VCC_1") (pintype "power_in"))
      (node (ref "IC7") (pin "1") (pinfunction "VCC_1") (pintype "power_in"))
      (node (ref "L1") (pin "1") (pinfunction "P$1_1") (pintype "passive"))
      (node (ref "L3") (pin "1") (pinfunction "P$1_1") (pintype "passive"))
      (node (ref "L5") (pin "1") (pinfunction "P$1_1") (pintype "passive"))
      (node (ref "POWER2") (pin "A") (pinfunction "ANODE_A") (pintype "passive"))
      (node (ref "R45") (pin "1") (pinfunction "P$1_1") (pintype "passive"))
      (node (ref "R46") (pin "2") (pinfunction "P$2_2") (pintype "passive"))
    )
    (net (code "2") (name "+5V") (class "Default")
      (node (ref "C40") (pin "2") (pinfunction "P$2_2") (pintype "passive"))
      (node (ref "IC100") (pin "OUT") (pinfunction "OUT_OUT") (pintype "power_in"))
      (node (ref "J5") (pin "2") (pinfunction "P$2_2") (pintype "passive"))
      (node (ref "POWER1") (pin "A") (pinfunction "ANODE_A") (pintype "passive"))
    )
    (net (code "3") (name "+24V") (class "Default")
      (node (ref "C100") (pin "+") (pinfunction "+_+") (pintype "passive"))
      (node (ref "C37") (pin "1") (pinfunction "P$1_1") (pintype "passive"))
      (node (ref "C41") (pin "1") (pinfunction "P$1_1") (pintype "passive"))
      (node (ref "D10") (pin "C") (pinfunction "K_C") (pintype "bidirectional"))
      (node (ref "D2") (pin "C") (pinfunction "K_C") (pintype "bidirectional"))
      (node (ref "FUSE1") (pin "2") (pinfunction "2_2") (pintype "passive"))
      (node (ref "IC100") (pin "IN") (pinfunction "IN_IN") (pintype "input"))
      (node (ref "IC101") (pin "IN") (pinfunction "IN_IN") (pintype "input"))
      (node (ref "J1") (pin "1") (pinfunction "1_1") (pintype "bidirectional"))
      (node (ref "J3") (pin "1") (pinfunction "1_1") (pintype "bidirectional"))
      (node (ref "POWER") (pin "A") (pinfunction "ANODE_A") (pintype "passive"))
    )
    (net (code "4") (name "3V3A") (class "Default")
      (node (ref "C2") (pin "1") (pinfunction "P$1_1") (pintype "passive"))
      (node (ref "C4") (pin "+") (pinfunction "+_+") (pintype "passive"))
      (node (ref "C6") (pin "2") (pinfunction "P$2_2") (pintype "passive"))
      (node (ref "C7") (pin "2") (pinfunction "P$2_2") (pintype "passive"))
      (node (ref "IC1") (pin "5") (pinfunction "VDDA3.3_5") (pintype "power_in"))
      (node (ref "J102") (pin "2") (pinfunction "TCT_2") (pintype "passive"))
      (node (ref "J102") (pin "5") (pinfunction "RCT_5") (pintype "passive"))
      (node (ref "J103") (pin "2") (pinfunction "TCT_2") (pintype "passive"))
      (node (ref "J103") (pin "5") (pinfunction "RCT_5") (pintype "passive"))
      (node (ref "L1") (pin "2") (pinfunction "P$2_2") (pintype "passive"))
    )
    (net (code "5") (name "3V3D") (class "Default")
      (node (ref "C15") (pin "2") (pinfunction "P$2_2") (pintype "passive"))
      (node (ref "C16") (pin "2") (pinfunction "P$2_2") (pintype "passive"))
      (node (ref "C17") (pin "+") (pinfunction "+_+") (pintype "passive"))
      (node (ref "C18") (pin "1") (pinfunction "P$1_1") (pintype "passive"))
      (node (ref "IC1") (pin "22") (pinfunction "VDDIO_22") (pintype "power_in"))
      (node (ref "IC1") (pin "40") (pinfunction "VDDIO_40") (pintype "power_in"))
      (node (ref "J102") (pin "GA") (pinfunction "GA_GA") (pintype "passive"))
      (node (ref "J102") (pin "YA") (pinfunction "YA_YA") (pintype "passive"))
      (node (ref "J103") (pin "GA") (pinfunction "GA_GA") (pintype "passive"))
      (node (ref "J103") (pin "YA") (pinfunction "YA_YA") (pintype "passive"))
      (node (ref "L3") (pin "2") (pinfunction "P$2_2") (pintype "passive"))
      (node (ref "R11") (pin "2") (pinfunction "P$2_2") (pintype "passive"))
      (node (ref "R12") (pin "1") (pinfunction "P$1_1") (pintype "passive"))
      (node (ref "R13") (pin "1") (pinfunction "P$1_1") (pintype "passive"))
      (node (ref "R15") (pin "1") (pinfunction "P$1_1") (pintype "passive"))
      (node (ref "R17") (pin "1") (pinfunction "P$1_1") (pintype "passive"))
    )
    (net (code "6") (name "24V_MON_1") (class "Default")
      (node (ref "IC2") (pin "67") (pinfunction "PA8_67") (pintype "bidirectional"))
      (node (ref "R25") (pin "1") (pinfunction "P$1_1") (pintype "passive"))
      (node (ref "R49") (pin "2") (pinfunction "P$2_2") (pintype "passive"))
    )
    (net (code "7") (name "24V_MON_2") (class "Default")
      (node (ref "IC2") (pin "66") (pinfunction "PC9_66") (pintype "bidirectional"))
      (node (ref "R22") (pin "1") (pinfunction "P$1_1") (pintype "passive"))
      (node (ref "R48") (pin "2") (pinfunction "P$2_2") (pintype "passive"))
    )
    (net (code "8") (name "24V_MON_3") (class "Default")
      (node (ref "IC2") (pin "65") (pinfunction "PC8_65") (pintype "bidirectional"))
      (node (ref "R19") (pin "1") (pinfunction "P$1_1") (pintype "passive"))
      (node (ref "R47") (pin "2") (pinfunction "P$2_2") (pintype "passive"))
    )
    (net (code "9") (name "24V_MON_4") (class "Default")
      (node (ref "IC2") (pin "91") (pinfunction "PB5_91") (pintype "bidirectional"))
      (node (ref "R23") (pin "1") (pinfunction "P$1_1") (pintype "passive"))
      (node (ref "R52") (pin "1") (pinfunction "P$1_1") (pintype "passive"))
    )
    (net (code "10") (name "24V_MON_5") (class "Default")
      (node (ref "IC2") (pin "90") (pinfunction "PB4_90") (pintype "bidirectional"))
      (node (ref "R26") (pin "1") (pinfunction "P$1_1") (pintype "passive"))
      (node (ref "R51") (pin "1") (pinfunction "P$1_1") (pintype "passive"))
    )
    (net (code "11") (name "24V_MON_6") (class "Default")
      (node (ref "IC2") (pin "88") (pinfunction "PD7_88") (pintype "bidirectional"))
      (node (ref "R28") (pin "1") (pinfunction "P$1_1") (pintype "passive"))
      (node (ref "R50") (pin "1") (pinfunction "P$1_1") (pintype "passive"))
    )
    (net (code "12") (name "AC_CTRL_1") (class "Default")
      (node (ref "IC2") (pin "69") (pinfunction "PA10_69") (pintype "bidirectional"))
      (node (ref "R30") (pin "1") (pinfunction "P$1_1") (pintype "passive"))
    )
    (net (code "13") (name "AC_CTRL_2") (class "Default")
      (node (ref "IC2") (pin "7") (pinfunction "PC13_7") (pintype "bidirectional"))
      (node (ref "R16") (pin "1") (pinfunction "P$1_1") (pintype "passive"))
    )
    (net (code "14") (name "AC_MON_1") (class "Default")
      (node (ref "IC2") (pin "68") (pinfunction "PA9_68") (pintype "bidirectional"))
      (node (ref "R27") (pin "1") (pinfunction "P$1_1") (pintype "passive"))
      (node (ref "R45") (pin "2") (pinfunction "P$2_2") (pintype "passive"))
    )
    (net (code "15") (name "AC_MON_2") (class "Default")
      (node (ref "IC2") (pin "96") (pinfunction "PB9_96") (pintype "bidirectional"))
      (node (ref "R20") (pin "1") (pinfunction "P$1_1") (pintype "passive"))
      (node (ref "R46") (pin "1") (pinfunction "P$1_1") (pintype "passive"))
    )
    (net (code "16") (name "CHASSIS") (class "Default")
      (node (ref "C1") (pin "2") (pinfunction "P$2_2") (pintype "passive"))
      (node (ref "J102") (pin "8") (pinfunction "CHASSIS_8") (pintype "passive"))
      (node (ref "J102") (pin "P$1") (pinfunction "CHASSIS_P$1") (pintype "passive"))
      (node (ref "J102") (pin "P$2") (pinfunction "CHASSIS_P$2") (pintype "passive"))
      (node (ref "J103") (pin "8") (pinfunction "CHASSIS_8") (pintype "passive"))
      (node (ref "J103") (pin "P$1") (pinfunction "CHASSIS_P$1") (pintype "passive"))
      (node (ref "J103") (pin "P$2") (pinfunction "CHASSIS_P$2") (pintype "passive"))
      (node (ref "SCREW1") (pin "P$1") (pinfunction "P$1_P$1") (pintype "passive"))
      (node (ref "SCREW2") (pin "P$1") (pinfunction "P$1_P$1") (pintype "passive"))
      (node (ref "SCREW3") (pin "P$1") (pinfunction "P$1_P$1") (pintype "passive"))
      (node (ref "SCREW4") (pin "P$1") (pinfunction "P$1_P$1") (pintype "passive"))
    )
    (net (code "17") (name "CPU+") (class "Default")
      (node (ref "C21") (pin "2") (pinfunction "P$2_2") (pintype "passive"))
      (node (ref "C24") (pin "2") (pinfunction "P$2_2") (pintype "passive"))
      (node (ref "C28") (pin "1") (pinfunction "P$1_1") (pintype "passive"))
      (node (ref "C31") (pin "+") (pinfunction "+_+") (pintype "passive"))
      (node (ref "C33") (pin "1") (pinfunction "P$1_1") (pintype "passive"))
      (node (ref "C34") (pin "1") (pinfunction "P$1_1") (pintype "passive"))
      (node (ref "C35") (pin "1") (pinfunction "P$1_1") (pintype "passive"))
      (node (ref "C36") (pin "2") (pinfunction "P$2_2") (pintype "passive"))
      (node (ref "C39") (pin "1") (pinfunction "P$1_1") (pintype "passive"))
      (node (ref "IC2") (pin "100") (pinfunction "VDD_100") (pintype "bidirectional"))
      (node (ref "IC2") (pin "11") (pinfunction "VDD_11") (pintype "bidirectional"))
      (node (ref "IC2") (pin "19") (pinfunction "VDD_19") (pintype "bidirectional"))
      (node (ref "IC2") (pin "28") (pinfunction "VDD_28") (pintype "bidirectional"))
      (node (ref "IC2") (pin "50") (pinfunction "VDD_50") (pintype "bidirectional"))
      (node (ref "IC2") (pin "6") (pinfunction "VBAT_6") (pintype "bidirectional"))
      (node (ref "IC2") (pin "75") (pinfunction "VDD_75") (pintype "bidirectional"))
      (node (ref "IC3") (pin "4") (pinfunction "VCC_4") (pintype "power_in"))
      (node (ref "J4") (pin "1") (pinfunction "TVCC_1") (pintype "bidirectional"))
      (node (ref "L4") (pin "2") (pinfunction "P$2_2") (pintype "passive"))
      (node (ref "L5") (pin "2") (pinfunction "P$2_2") (pintype "passive"))
      (node (ref "LED1") (pin "A") (pinfunction "ANODE_A") (pintype "passive"))
      (node (ref "LED2") (pin "A") (pinfunction "ANODE_A") (pintype "passive"))
      (node (ref "R29") (pin "1") (pinfunction "P$1_1") (pintype "passive"))
      (node (ref "R31") (pin "1") (pinfunction "P$1_1") (pintype "passive"))
    )
    (net (code "18") (name "DISP_A") (class "Default")
      (node (ref "IC2") (pin "5") (pinfunction "PE6_5") (pintype "bidirectional"))
      (node (ref "J2") (pin "9") (pinfunction "9_9") (pintype "passive"))
    )
    (net (code "19") (name "DISP_B") (class "Default")
      (node (ref "IC2") (pin "4") (pinfunction "PE5_4") (pintype "bidirectional"))
      (node (ref "J2") (pin "10") (pinfunction "10_10") (pintype "passive"))
    )
    (net (code "20") (name "DISP_B0") (class "Default")
      (node (ref "IC2") (pin "40") (pinfunction "PE9_40") (pintype "bidirectional"))
      (node (ref "J2") (pin "3") (pinfunction "3_3") (pintype "passive"))
    )
    (net (code "21") (name "DISP_B1") (class "Default")
      (node (ref "IC2") (pin "43") (pinfunction "PE12_43") (pintype "bidirectional"))
      (node (ref "J2") (pin "7") (pinfunction "7_7") (pintype "passive"))
    )
    (net (code "22") (name "DISP_C") (class "Default")
      (node (ref "IC2") (pin "3") (pinfunction "PE4_3") (pintype "bidirectional"))
      (node (ref "J2") (pin "11") (pinfunction "11_11") (pintype "passive"))
    )
    (net (code "23") (name "DISP_CLK") (class "Default")
      (node (ref "IC2") (pin "1") (pinfunction "PE2_1") (pintype "bidirectional"))
      (node (ref "J2") (pin "13") (pinfunction "13_13") (pintype "passive"))
    )
    (net (code "24") (name "DISP_D") (class "Default")
      (node (ref "IC2") (pin "2") (pinfunction "PE3_2") (pintype "bidirectional"))
      (node (ref "J2") (pin "12") (pinfunction "12_12") (pintype "passive"))
    )
    (net (code "25") (name "DISP_G0") (class "Default")
      (node (ref "IC2") (pin "39") (pinfunction "PE8_39") (pintype "bidirectional"))
      (node (ref "J2") (pin "2") (pinfunction "2_2") (pintype "passive"))
    )
    (net (code "26") (name "DISP_G1") (class "Default")
      (node (ref "IC2") (pin "42") (pinfunction "PE11_42") (pintype "bidirectional"))
      (node (ref "J2") (pin "6") (pinfunction "6_6") (pintype "passive"))
    )
    (net (code "27") (name "DISP_OE") (class "Default")
      (node (ref "IC2") (pin "97") (pinfunction "PE0_97") (pintype "bidirectional"))
      (node (ref "J2") (pin "15") (pinfunction "15_15") (pintype "passive"))
    )
    (net (code "28") (name "DISP_R0") (class "Default")
      (node (ref "IC2") (pin "38") (pinfunction "PE7_38") (pintype "bidirectional"))
      (node (ref "J2") (pin "1") (pinfunction "1_1") (pintype "passive"))
    )
    (net (code "29") (name "DISP_R1") (class "Default")
      (node (ref "IC2") (pin "41") (pinfunction "PE10_41") (pintype "bidirectional"))
      (node (ref "J2") (pin "5") (pinfunction "5_5") (pintype "passive"))
    )
    (net (code "30") (name "DISP_STB") (class "Default")
      (node (ref "IC2") (pin "98") (pinfunction "PE1_98") (pintype "bidirectional"))
      (node (ref "J2") (pin "14") (pinfunction "14_14") (pintype "passive"))
    )
    (net (code "31") (name "GND") (class "Default")
      (node (ref "C1") (pin "1") (pinfunction "P$1_1") (pintype "passive"))
      (node (ref "C10") (pin "1") (pinfunction "P$1_1") (pintype "passive"))
      (node (ref "C100") (pin "-") (pinfunction "-_-") (pintype "passive"))
      (node (ref "C11") (pin "1") (pinfunction "P$1_1") (pintype "passive"))
      (node (ref "C12") (pin "1") (pinfunction "P$1_1") (pintype "passive"))
      (node (ref "C13") (pin "1") (pinfunction "P$1_1") (pintype "passive"))
      (node (ref "C14") (pin "1") (pinfunction "P$1_1") (pintype "passive"))
      (node (ref "C15") (pin "1") (pinfunction "P$1_1") (pintype "passive"))
      (node (ref "C16") (pin "1") (pinfunction "P$1_1") (pintype "passive"))
      (node (ref "C17") (pin "-") (pinfunction "-_-") (pintype "passive"))
      (node (ref "C18") (pin "2") (pinfunction "P$2_2") (pintype "passive"))
      (node (ref "C19") (pin "-") (pinfunction "-_-") (pintype "passive"))
      (node (ref "C2") (pin "2") (pinfunction "P$2_2") (pintype "passive"))
      (node (ref "C20") (pin "2") (pinfunction "P$2_2") (pintype "passive"))
      (node (ref "C21") (pin "1") (pinfunction "P$1_1") (pintype "passive"))
      (node (ref "C22") (pin "1") (pinfunction "P$1_1") (pintype "passive"))
      (node (ref "C23") (pin "2") (pinfunction "P$2_2") (pintype "passive"))
      (node (ref "C24") (pin "1") (pinfunction "P$1_1") (pintype "passive"))
      (node (ref "C25") (pin "2") (pinfunction "P$2_2") (pintype "passive"))
      (node (ref "C26") (pin "2") (pinfunction "P$2_2") (pintype "passive"))
      (node (ref "C27") (pin "2") (pinfunction "P$2_2") (pintype "passive"))
      (node (ref "C28") (pin "2") (pinfunction "P$2_2") (pintype "passive"))
      (node (ref "C29") (pin "1") (pinfunction "P$1_1") (pintype "passive"))
      (node (ref "C3") (pin "-") (pinfunction "-_-") (pintype "passive"))
      (node (ref "C30") (pin "2") (pinfunction "P$2_2") (pintype "passive"))
      (node (ref "C31") (pin "-") (pinfunction "-_-") (pintype "passive"))
      (node (ref "C32") (pin "2") (pinfunction "P$2_2") (pintype "passive"))
      (node (ref "C33") (pin "2") (pinfunction "P$2_2") (pintype "passive"))
      (node (ref "C34") (pin "2") (pinfunction "P$2_2") (pintype "passive"))
      (node (ref "C35") (pin "2") (pinfunction "P$2_2") (pintype "passive"))
      (node (ref "C36") (pin "1") (pinfunction "P$1_1") (pintype "passive"))
      (node (ref "C37") (pin "2") (pinfunction "P$2_2") (pintype "passive"))
      (node (ref "C38") (pin "1") (pinfunction "P$1_1") (pintype "passive"))
      (node (ref "C39") (pin "2") (pinfunction "P$2_2") (pintype "passive"))
      (node (ref "C4") (pin "-") (pinfunction "-_-") (pintype "passive"))
      (node (ref "C40") (pin "1") (pinfunction "P$1_1") (pintype "passive"))
      (node (ref "C41") (pin "2") (pinfunction "P$2_2") (pintype "passive"))
      (node (ref "C42") (pin "1") (pinfunction "P$1_1") (pintype "passive"))
      (node (ref "C43") (pin "1") (pinfunction "P$1_1") (pintype "passive"))
      (node (ref "C44") (pin "1") (pinfunction "P$1_1") (pintype "passive"))
      (node (ref "C45") (pin "1") (pinfunction "P$1_1") (pintype "passive"))
      (node (ref "C5") (pin "1") (pinfunction "P$1_1") (pintype "passive"))
      (node (ref "C6") (pin "1") (pinfunction "P$1_1") (pintype "passive"))
      (node (ref "C7") (pin "1") (pinfunction "P$1_1") (pintype "passive"))
      (node (ref "C8") (pin "2") (pinfunction "P$2_2") (pintype "passive"))
      (node (ref "C9") (pin "2") (pinfunction "P$2_2") (pintype "passive"))
      (node (ref "IC1") (pin "10") (pinfunction "AGND_10") (pintype "power_in"))
      (node (ref "IC1") (pin "21") (pinfunction "GND_21") (pintype "power_in"))
      (node (ref "IC1") (pin "31") (pinfunction "GND_31") (pintype "power_in"))
      (node (ref "IC1") (pin "41") (pinfunction "GND_41") (pintype "power_in"))
      (node (ref "IC100") (pin "GND") (pinfunction "GND_GND") (pintype "input"))
      (node (ref "IC101") (pin "GND") (pinfunction "GND_GND") (pintype "input"))
      (node (ref "IC2") (pin "10") (pinfunction "VSS_10") (pintype "bidirectional"))
      (node (ref "IC2") (pin "20") (pinfunction "VSSA_20") (pintype "bidirectional"))
      (node (ref "IC2") (pin "27") (pinfunction "VSS_27") (pintype "bidirectional"))
      (node (ref "IC2") (pin "74") (pinfunction "VSS_74") (pintype "bidirectional"))
      (node (ref "IC2") (pin "94") (pinfunction "BOOT0_94") (pintype "bidirectional"))
      (node (ref "IC2") (pin "99") (pinfunction "VSS_99") (pintype "bidirectional"))
      (node (ref "IC3") (pin "2") (pinfunction "GND_2") (pintype "power_in"))
      (node (ref "IC4") (pin "4") (pinfunction "GND_4") (pintype "power_in"))
      (node (ref "IC5") (pin "4") (pinfunction "GND_4") (pintype "power_in"))
      (node (ref "IC6") (pin "4") (pinfunction "GND_4") (pintype "power_in"))
      (node (ref "IC7") (pin "4") (pinfunction "GND_4") (pintype "power_in"))
      (node (ref "J1") (pin "3") (pinfunction "3_3") (pintype "bidirectional"))
      (node (ref "J1") (pin "5") (pinfunction "5_5") (pintype "bidirectional"))
      (node (ref "J1") (pin "7") (pinfunction "7_7") (pintype "bidirectional"))
      (node (ref "J1") (pin "9") (pinfunction "9_9") (pintype "bidirectional"))
      (node (ref "J100") (pin "2") (pinfunction "SLEEVE_2") (pintype "bidirectional"))
      (node (ref "J101") (pin "A1") (pinfunction "1_A1") (pintype "bidirectional"))
      (node (ref "J101") (pin "B1") (pinfunction "1_B1") (pintype "bidirectional"))
      (node (ref "J101") (pin "C1") (pinfunction "1_C1") (pintype "bidirectional"))
      (node (ref "J101") (pin "D1") (pinfunction "1_D1") (pintype "bidirectional"))
      (node (ref "J2") (pin "16") (pinfunction "16_16") (pintype "passive"))
      (node (ref "J2") (pin "4") (pinfunction "4_4") (pintype "passive"))
      (node (ref "J2") (pin "8") (pinfunction "8_8") (pintype "passive"))
      (node (ref "J3") (pin "3") (pinfunction "3_3") (pintype "bidirectional"))
      (node (ref "J3") (pin "5") (pinfunction "5_5") (pintype "bidirectional"))
      (node (ref "J3") (pin "7") (pinfunction "7_7") (pintype "bidirectional"))
      (node (ref "J3") (pin "9") (pinfunction "9_9") (pintype "bidirectional"))
      (node (ref "J4") (pin "3") (pinfunction "GND_3") (pintype "bidirectional"))
      (node (ref "J5") (pin "1") (pinfunction "P$1_1") (pintype "passive"))
      (node (ref "Q2") (pin "2") (pinfunction "S_2") (pintype "bidirectional"))
      (node (ref "Q9") (pin "2") (pinfunction "S_2") (pintype "bidirectional"))
      (node (ref "R1") (pin "2") (pinfunction "P$2_2") (pintype "passive"))
      (node (ref "R10") (pin "1") (pinfunction "P$1_1") (pintype "passive"))
      (node (ref "R32") (pin "2") (pinfunction "P$2_2") (pintype "passive"))
      (node (ref "R33") (pin "2") (pinfunction "P$2_2") (pintype "passive"))
      (node (ref "R34") (pin "2") (pinfunction "P$2_2") (pintype "passive"))
      (node (ref "R41") (pin "2") (pinfunction "P$2_2") (pintype "passive"))
      (node (ref "R42") (pin "2") (pinfunction "P$2_2") (pintype "passive"))
      (node (ref "R43") (pin "2") (pinfunction "P$2_2") (pintype "passive"))
      (node (ref "R44") (pin "2") (pinfunction "P$2_2") (pintype "passive"))
      (node (ref "R47") (pin "1") (pinfunction "P$1_1") (pintype "passive"))
      (node (ref "R48") (pin "1") (pinfunction "P$1_1") (pintype "passive"))
      (node (ref "R49") (pin "1") (pinfunction "P$1_1") (pintype "passive"))
      (node (ref "R50") (pin "2") (pinfunction "P$2_2") (pintype "passive"))
      (node (ref "R51") (pin "2") (pinfunction "P$2_2") (pintype "passive"))
      (node (ref "R52") (pin "2") (pinfunction "P$2_2") (pintype "passive"))
      (node (ref "S1") (pin "C") (pinfunction "COM_C") (pintype "bidirectional"))
      (node (ref "S1") (pin "C@2") (pinfunction "COM_C@2") (pintype "bidirectional"))
      (node (ref "S2") (pin "C") (pinfunction "COM_C") (pintype "bidirectional"))
      (node (ref "S2") (pin "C@2") (pinfunction "COM_C@2") (pintype "bidirectional"))
    )
    (net (code "32") (name "HEX1") (class "Default")
      (node (ref "IC2") (pin "61") (pinfunction "PD14_61") (pintype "bidirectional"))
      (node (ref "S2") (pin "1") (pinfunction "1_1") (pintype "bidirectional"))
    )
    (net (code "33") (name "HEX2") (class "Default")
      (node (ref "IC2") (pin "60") (pinfunction "PD13_60") (pintype "bidirectional"))
      (node (ref "S2") (pin "2") (pinfunction "2_2") (pintype "bidirectional"))
    )
    (net (code "34") (name "HEX4") (class "Default")
      (node (ref "IC2") (pin "59") (pinfunction "PD12_59") (pintype "bidirectional"))
      (node (ref "S2") (pin "4") (pinfunction "4_4") (pintype "bidirectional"))
    )
    (net (code "35") (name "HEX8") (class "Default")
      (node (ref "IC2") (pin "62") (pinfunction "PD15_62") (pintype "bidirectional"))
      (node (ref "S2") (pin "8") (pinfunction "8_8") (pintype "bidirectional"))
    )
    (net (code "36") (name "HEX16") (class "Default")
      (node (ref "IC2") (pin "57") (pinfunction "PD10_57") (pintype "bidirectional"))
      (node (ref "S1") (pin "1") (pinfunction "1_1") (pintype "bidirectional"))
    )
    (net (code "37") (name "HEX32") (class "Default")
      (node (ref "IC2") (pin "56") (pinfunction "PD9_56") (pintype "bidirectional"))
      (node (ref "S1") (pin "2") (pinfunction "2_2") (pintype "bidirectional"))
    )
    (net (code "38") (name "HEX64") (class "Default")
      (node (ref "IC2") (pin "55") (pinfunction "PD8_55") (pintype "bidirectional"))
      (node (ref "S1") (pin "4") (pinfunction "4_4") (pintype "bidirectional"))
    )
    (net (code "39") (name "HEX128") (class "Default")
      (node (ref "IC2") (pin "58") (pinfunction "PD11_58") (pintype "bidirectional"))
      (node (ref "S1") (pin "8") (pinfunction "8_8") (pintype "bidirectional"))
    )
    (net (code "40") (name "I2C1_SCL") (class "Default")
      (node (ref "IC2") (pin "92") (pinfunction "PB6_92") (pintype "bidirectional"))
      (node (ref "IC3") (pin "1") (pinfunction "SCL_1") (pintype "open_collector"))
      (node (ref "R31") (pin "2") (pinfunction "P$2_2") (pintype "passive"))
    )
    (net (code "41") (name "I2C1_SDA") (class "Default")
      (node (ref "IC2") (pin "93") (pinfunction "PB7_93") (pintype "bidirectional"))
      (node (ref "IC3") (pin "3") (pinfunction "SDA_3") (pintype "open_collector"))
      (node (ref "R29") (pin "2") (pinfunction "P$2_2") (pintype "passive"))
    )
    (net (code "42") (name "MII_COL") (class "Default")
      (node (ref "IC1") (pin "33") (pinfunction "SCOL3_33") (pintype "bidirectional"))
      (node (ref "IC2") (pin "26") (pinfunction "PA3_26") (pintype "bidirectional"))
    )
    (net (code "43") (name "MII_CRS") (class "Default")
      (node (ref "IC1") (pin "34") (pinfunction "SCRS3_34") (pintype "bidirectional"))
      (node (ref "IC2") (pin "23") (pinfunction "PA0_23") (pintype "bidirectional"))
    )
    (net (code "44") (name "MII_MDC") (class "Default")
      (node (ref "IC1") (pin "36") (pinfunction "SCL_MDC_36") (pintype "bidirectional"))
      (node (ref "IC2") (pin "16") (pinfunction "PC1_16") (pintype "bidirectional"))
      (node (ref "R15") (pin "2") (pinfunction "P$2_2") (pintype "passive"))
    )
    (net (code "45") (name "MII_MDIO") (class "Default")
      (node (ref "IC1") (pin "37") (pinfunction "SDA_MDIO_37") (pintype "bidirectional"))
      (node (ref "IC2") (pin "25") (pinfunction "PA2_25") (pintype "bidirectional"))
      (node (ref "R17") (pin "2") (pinfunction "P$2_2") (pintype "passive"))
    )
    (net (code "46") (name "MII_RXD0") (class "Default")
      (node (ref "IC1") (pin "29") (pinfunction "SMRXD30_29") (pintype "bidirectional"))
      (node (ref "IC2") (pin "33") (pinfunction "PC4_33") (pintype "bidirectional"))
    )
    (net (code "47") (name "MII_RXD1") (class "Default")
      (node (ref "IC1") (pin "28") (pinfunction "SMRXD31_28") (pintype "bidirectional"))
      (node (ref "IC2") (pin "34") (pinfunction "PC5_34") (pintype "bidirectional"))
    )
    (net (code "48") (name "MII_RXD2") (class "Default")
      (node (ref "IC1") (pin "27") (pinfunction "SMRXD32_27") (pintype "bidirectional"))
      (node (ref "IC2") (pin "35") (pinfunction "PB0_35") (pintype "bidirectional"))
    )
    (net (code "49") (name "MII_RXD3") (class "Default")
      (node (ref "IC1") (pin "26") (pinfunction "SMRXD33/REFCLKO_3_26") (pintype "bidirectional"))
      (node (ref "IC2") (pin "36") (pinfunction "PB1_36") (pintype "bidirectional"))
    )
    (net (code "50") (name "MII_RX_CLK") (class "Default")
      (node (ref "IC2") (pin "24") (pinfunction "PA1_24") (pintype "bidirectional"))
      (node (ref "R18") (pin "2") (pinfunction "P$2_2") (pintype "passive"))
    )
    (net (code "51") (name "MII_RX_DV") (class "Default")
      (node (ref "IC1") (pin "25") (pinfunction "SMRXDV3_25") (pintype "bidirectional"))
      (node (ref "IC2") (pin "32") (pinfunction "PA7_32") (pintype "bidirectional"))
    )
    (net (code "52") (name "MII_TXD0") (class "Default")
      (node (ref "IC1") (pin "20") (pinfunction "SMTXD30_20") (pintype "input"))
      (node (ref "IC2") (pin "51") (pinfunction "PB12_51") (pintype "bidirectional"))
    )
    (net (code "53") (name "MII_TXD1") (class "Default")
      (node (ref "IC1") (pin "19") (pinfunction "SMTXD31_19") (pintype "input"))
      (node (ref "IC2") (pin "52") (pinfunction "PB13_52") (pintype "bidirectional"))
    )
    (net (code "54") (name "MII_TXD2") (class "Default")
      (node (ref "IC1") (pin "18") (pinfunction "SMTXD32_18") (pintype "input"))
      (node (ref "IC2") (pin "17") (pinfunction "PC2_17") (pintype "bidirectional"))
    )
    (net (code "55") (name "MII_TXD3") (class "Default")
      (node (ref "IC1") (pin "17") (pinfunction "SMTXD33/EN_REFCLKO_3_17") (pintype "input"))
      (node (ref "IC2") (pin "95") (pinfunction "PB8_95") (pintype "bidirectional"))
    )
    (net (code "56") (name "MII_TX_CLK") (class "Default")
      (node (ref "IC2") (pin "18") (pinfunction "PC3_18") (pintype "bidirectional"))
      (node (ref "R14") (pin "2") (pinfunction "P$2_2") (pintype "passive"))
    )
    (net (code "57") (name "MII_TX_EN") (class "Default")
      (node (ref "IC1") (pin "16") (pinfunction "SMTXEN3_16") (pintype "input"))
      (node (ref "IC2") (pin "48") (pinfunction "PB11_48") (pintype "bidirectional"))
    )
    (net (code "58") (name "Net-(C5-P$2)") (class "Default")
      (node (ref "C3") (pin "+") (pinfunction "+_+") (pintype "passive"))
      (node (ref "C5") (pin "2") (pinfunction "P$2_2") (pintype "passive"))
      (node (ref "IC1") (pin "7") (pinfunction "VDDA1.8_7") (pintype "power_in"))
      (node (ref "L2") (pin "1") (pinfunction "P$1_1") (pintype "passive"))
    )
    (net (code "59") (name "Net-(C8-P$1)") (class "Default")
      (node (ref "C8") (pin "1") (pinfunction "P$1_1") (pintype "passive"))
      (node (ref "R2") (pin "1") (pinfunction "P$1_1") (pintype "passive"))
      (node (ref "R4") (pin "1") (pinfunction "P$1_1") (pintype "passive"))
    )
    (net (code "60") (name "Net-(C9-P$1)") (class "Default")
      (node (ref "C9") (pin "1") (pinfunction "P$1_1") (pintype "passive"))
      (node (ref "R3") (pin "1") (pinfunction "P$1_1") (pintype "passive"))
      (node (ref "R5") (pin "1") (pinfunction "P$1_1") (pintype "passive"))
    )
    (net (code "61") (name "Net-(C10-P$2)") (class "Default")
      (node (ref "C10") (pin "2") (pinfunction "P$2_2") (pintype "passive"))
      (node (ref "R6") (pin "2") (pinfunction "P$2_2") (pintype "passive"))
      (node (ref "R8") (pin "2") (pinfunction "P$2_2") (pintype "passive"))
    )
    (net (code "62") (name "Net-(C11-P$2)") (class "Default")
      (node (ref "C11") (pin "2") (pinfunction "P$2_2") (pintype "passive"))
      (node (ref "R7") (pin "2") (pinfunction "P$2_2") (pintype "passive"))
      (node (ref "R9") (pin "2") (pinfunction "P$2_2") (pintype "passive"))
    )
    (net (code "63") (name "Net-(C12-P$2)") (class "Default")
      (node (ref "C12") (pin "2") (pinfunction "P$2_2") (pintype "passive"))
      (node (ref "IC1") (pin "14") (pinfunction "X1_14") (pintype "input"))
      (node (ref "Y1") (pin "2") (pinfunction "P$2_2") (pintype "bidirectional"))
    )
    (net (code "64") (name "Net-(C13-P$2)") (class "Default")
      (node (ref "C13") (pin "2") (pinfunction "P$2_2") (pintype "passive"))
      (node (ref "IC1") (pin "47") (pinfunction "~{RSTN}_47") (pintype "input"))
      (node (ref "R11") (pin "1") (pinfunction "P$1_1") (pintype "passive"))
    )
    (net (code "65") (name "Net-(C14-P$2)") (class "Default")
      (node (ref "C14") (pin "2") (pinfunction "P$2_2") (pintype "passive"))
      (node (ref "IC1") (pin "15") (pinfunction "X2_15") (pintype "output"))
      (node (ref "Y1") (pin "1") (pinfunction "P$1_1") (pintype "bidirectional"))
    )
    (net (code "66") (name "Net-(C20-P$1)") (class "Default")
      (node (ref "C19") (pin "+") (pinfunction "+_+") (pintype "passive"))
      (node (ref "C20") (pin "1") (pinfunction "P$1_1") (pintype "passive"))
      (node (ref "IC1") (pin "32") (pinfunction "VDDC_32") (pintype "power_in"))
      (node (ref "IC1") (pin "42") (pinfunction "VDDCO_42") (pintype "power_in"))
      (node (ref "L2") (pin "2") (pinfunction "P$2_2") (pintype "passive"))
    )
    (net (code "67") (name "Net-(C22-P$2)") (class "Default")
      (node (ref "C22") (pin "2") (pinfunction "P$2_2") (pintype "passive"))
      (node (ref "IC2") (pin "49") (pinfunction "VCAP_1_49") (pintype "bidirectional"))
    )
    (net (code "68") (name "Net-(C23-P$1)") (class "Default")
      (node (ref "C23") (pin "1") (pinfunction "P$1_1") (pintype "passive"))
      (node (ref "C25") (pin "1") (pinfunction "P$1_1") (pintype "passive"))
      (node (ref "IC2") (pin "22") (pinfunction "VDDA_22") (pintype "bidirectional"))
      (node (ref "L4") (pin "1") (pinfunction "P$1_1") (pintype "passive"))
      (node (ref "R21") (pin "1") (pinfunction "P$1_1") (pintype "passive"))
    )
    (net (code "69") (name "Net-(C26-P$1)") (class "Default")
      (node (ref "C26") (pin "1") (pinfunction "P$1_1") (pintype "passive"))
      (node (ref "C27") (pin "1") (pinfunction "P$1_1") (pintype "passive"))
      (node (ref "IC2") (pin "21") (pinfunction "VREF+_21") (pintype "bidirectional"))
      (node (ref "R21") (pin "2") (pinfunction "P$2_2") (pintype "passive"))
    )
    (net (code "70") (name "Net-(C29-P$2)") (class "Default")
      (node (ref "C29") (pin "2") (pinfunction "P$2_2") (pintype "passive"))
      (node (ref "IC2") (pin "13") (pinfunction "PH1_13") (pintype "bidirectional"))
      (node (ref "Y2") (pin "1") (pinfunction "P$1_1") (pintype "bidirectional"))
    )
    (net (code "71") (name "Net-(C30-P$1)") (class "Default")
      (node (ref "C30") (pin "1") (pinfunction "P$1_1") (pintype "passive"))
      (node (ref "R24") (pin "1") (pinfunction "P$1_1") (pintype "passive"))
      (node (ref "Y2") (pin "2") (pinfunction "P$2_2") (pintype "bidirectional"))
    )
    (net (code "72") (name "Net-(C32-P$1)") (class "Default")
      (node (ref "C32") (pin "1") (pinfunction "P$1_1") (pintype "passive"))
      (node (ref "IC2") (pin "73") (pinfunction "VCAP_2_73") (pintype "bidirectional"))
    )
    (net (code "73") (name "Net-(D11-K)") (class "Default")
      (node (ref "D11") (pin "C") (pinfunction "K_C") (pintype "bidirectional"))
      (node (ref "L10") (pin "2") (pinfunction "P$2_2") (pintype "passive"))
    )
    (net (code "74") (name "Net-(D12-K)") (class "Default")
      (node (ref "D12") (pin "C") (pinfunction "K_C") (pintype "bidirectional"))
      (node (ref "L6") (pin "2") (pinfunction "P$2_2") (pintype "passive"))
    )
    (net (code "75") (name "Net-(D13-K)") (class "Default")
      (node (ref "D13") (pin "C") (pinfunction "K_C") (pintype "bidirectional"))
      (node (ref "L7") (pin "2") (pinfunction "P$2_2") (pintype "passive"))
    )
    (net (code "76") (name "Net-(D14-K)") (class "Default")
      (node (ref "D14") (pin "C") (pinfunction "K_C") (pintype "bidirectional"))
      (node (ref "L8") (pin "2") (pinfunction "P$2_2") (pintype "passive"))
    )
    (net (code "77") (name "Net-(D15-K)") (class "Default")
      (node (ref "D15") (pin "C") (pinfunction "K_C") (pintype "bidirectional"))
      (node (ref "L9") (pin "2") (pinfunction "P$2_2") (pintype "passive"))
    )
    (net (code "78") (name "Net-(IC1-FXSD1)") (class "Default")
      (node (ref "IC1") (pin "48") (pinfunction "FXSD1_48") (pintype "input"))
      (node (ref "R10") (pin "2") (pinfunction "P$2_2") (pintype "passive"))
    )
    (net (code "79") (name "Net-(IC1-ISET)") (class "Default")
      (node (ref "IC1") (pin "6") (pinfunction "ISET_6") (pintype "output"))
      (node (ref "R1") (pin "1") (pinfunction "P$1_1") (pintype "passive"))
    )
    (net (code "80") (name "Net-(IC1-RXM1)") (class "Default")
      (node (ref "IC1") (pin "1") (pinfunction "RXM1_1") (pintype "bidirectional"))
      (node (ref "J102") (pin "6") (pinfunction "RD-_6") (pintype "passive"))
      (node (ref "R9") (pin "1") (pinfunction "P$1_1") (pintype "passive"))
    )
    (net (code "81") (name "Net-(IC1-RXM2)") (class "Default")
      (node (ref "IC1") (pin "8") (pinfunction "RXM2_8") (pintype "bidirectional"))
      (node (ref "J103") (pin "6") (pinfunction "RD-_6") (pintype "passive"))
      (node (ref "R2") (pin "2") (pinfunction "P$2_2") (pintype "passive"))
    )
    (net (code "82") (name "Net-(IC1-RXP1)") (class "Default")
      (node (ref "IC1") (pin "2") (pinfunction "RXP1_2") (pintype "bidirectional"))
      (node (ref "J102") (pin "4") (pinfunction "RD+_4") (pintype "passive"))
      (node (ref "R7") (pin "1") (pinfunction "P$1_1") (pintype "passive"))
    )
    (net (code "83") (name "Net-(IC1-RXP2)") (class "Default")
      (node (ref "IC1") (pin "9") (pinfunction "RXP2_9") (pintype "bidirectional"))
      (node (ref "J103") (pin "4") (pinfunction "RD+_4") (pintype "passive"))
      (node (ref "R4") (pin "2") (pinfunction "P$2_2") (pintype "passive"))
    )
    (net (code "84") (name "Net-(IC1-SMRXC3)") (class "Default")
      (node (ref "IC1") (pin "30") (pinfunction "SMRXC3_30") (pintype "bidirectional"))
      (node (ref "R18") (pin "1") (pinfunction "P$1_1") (pintype "passive"))
    )
    (net (code "85") (name "Net-(IC1-SMTXC3{slash}REFCLKI_3)") (class "Default")
      (node (ref "IC1") (pin "23") (pinfunction "SMTXC3/REFCLKI_3_23") (pintype "bidirectional"))
      (node (ref "R14") (pin "1") (pinfunction "P$1_1") (pintype "passive"))
    )
    (net (code "86") (name "Net-(IC1-SPISN)") (class "Default")
      (node (ref "IC1") (pin "39") (pinfunction "SPISN_39") (pintype "input"))
      (node (ref "R12") (pin "2") (pinfunction "P$2_2") (pintype "passive"))
    )
    (net (code "87") (name "Net-(IC1-TXM1)") (class "Default")
      (node (ref "IC1") (pin "3") (pinfunction "TXM1_3") (pintype "bidirectional"))
      (node (ref "J102") (pin "3") (pinfunction "TD-_3") (pintype "passive"))
      (node (ref "R5") (pin "2") (pinfunction "P$2_2") (pintype "passive"))
    )
    (net (code "88") (name "Net-(IC1-TXM2)") (class "Default")
      (node (ref "IC1") (pin "11") (pinfunction "TXM2_11") (pintype "bidirectional"))
      (node (ref "J103") (pin "3") (pinfunction "TD-_3") (pintype "passive"))
      (node (ref "R6") (pin "1") (pinfunction "P$1_1") (pintype "passive"))
    )
    (net (code "89") (name "Net-(IC1-TXP1)") (class "Default")
      (node (ref "IC1") (pin "4") (pinfunction "TXP1_4") (pintype "bidirectional"))
      (node (ref "J102") (pin "1") (pinfunction "TD+_1") (pintype "passive"))
      (node (ref "R3") (pin "2") (pinfunction "P$2_2") (pintype "passive"))
    )
    (net (code "90") (name "Net-(IC1-TXP2)") (class "Default")
      (node (ref "IC1") (pin "12") (pinfunction "TXP2_12") (pintype "bidirectional"))
      (node (ref "J103") (pin "1") (pinfunction "TD+_1") (pintype "passive"))
      (node (ref "R8") (pin "1") (pinfunction "P$1_1") (pintype "passive"))
    )
    (net (code "91") (name "Net-(IC1-~{INTRN})") (class "Default")
      (node (ref "IC1") (pin "35") (pinfunction "~{INTRN}_35") (pintype "output"))
      (node (ref "R13") (pin "2") (pinfunction "P$2_2") (pintype "passive"))
    )
    (net (code "92") (name "Net-(IC2E-PE13)") (class "Default")
      (node (ref "IC2") (pin "44") (pinfunction "PE13_44") (pintype "bidirectional"))
      (node (ref "R35") (pin "2") (pinfunction "P$2_2") (pintype "passive"))
    )
    (net (code "93") (name "Net-(IC2E-PE14)") (class "Default")
      (node (ref "IC2") (pin "45") (pinfunction "PE14_45") (pintype "bidirectional"))
      (node (ref "R36") (pin "2") (pinfunction "P$2_2") (pintype "passive"))
    )
    (net (code "94") (name "Net-(IC2F-PH0)") (class "Default")
      (node (ref "IC2") (pin "12") (pinfunction "PH0_12") (pintype "bidirectional"))
      (node (ref "R24") (pin "2") (pinfunction "P$2_2") (pintype "passive"))
    )
    (net (code "95") (name "Net-(IC4-A)") (class "Default")
      (node (ref "IC4") (pin "8") (pinfunction "A_8") (pintype "bidirectional"))
      (node (ref "J101") (pin "D5") (pinfunction "5_D5") (pintype "bidirectional"))
      (node (ref "R37") (pin "2") (pinfunction "P$2_2") (pintype "passive"))
    )
    (net (code "96") (name "Net-(IC4-B)") (class "Default")
      (node (ref "IC4") (pin "7") (pinfunction "B_7") (pintype "bidirectional"))
      (node (ref "J101") (pin "D2") (pinfunction "2_D2") (pintype "bidirectional"))
      (node (ref "R37") (pin "1") (pinfunction "P$1_1") (pintype "passive"))
    )
    (net (code "97") (name "Net-(IC4-Y)") (class "Default")
      (node (ref "IC4") (pin "5") (pinfunction "Y_5") (pintype "bidirectional"))
      (node (ref "J101") (pin "D3") (pinfunction "3_D3") (pintype "bidirectional"))
    )
    (net (code "98") (name "Net-(IC4-Z)") (class "Default")
      (node (ref "IC4") (pin "6") (pinfunction "Z_6") (pintype "bidirectional"))
      (node (ref "J101") (pin "D4") (pinfunction "4_D4") (pintype "bidirectional"))
    )
    (net (code "99") (name "Net-(IC5-A)") (class "Default")
      (node (ref "IC5") (pin "8") (pinfunction "A_8") (pintype "bidirectional"))
      (node (ref "J101") (pin "C5") (pinfunction "5_C5") (pintype "bidirectional"))
      (node (ref "R38") (pin "2") (pinfunction "P$2_2") (pintype "passive"))
    )
    (net (code "100") (name "Net-(IC5-B)") (class "Default")
      (node (ref "IC5") (pin "7") (pinfunction "B_7") (pintype "bidirectional"))
      (node (ref "J101") (pin "C2") (pinfunction "2_C2") (pintype "bidirectional"))
      (node (ref "R38") (pin "1") (pinfunction "P$1_1") (pintype "passive"))
    )
    (net (code "101") (name "Net-(IC5-Y)") (class "Default")
      (node (ref "IC5") (pin "5") (pinfunction "Y_5") (pintype "bidirectional"))
      (node (ref "J101") (pin "C3") (pinfunction "3_C3") (pintype "bidirectional"))
    )
    (net (code "102") (name "Net-(IC5-Z)") (class "Default")
      (node (ref "IC5") (pin "6") (pinfunction "Z_6") (pintype "bidirectional"))
      (node (ref "J101") (pin "C4") (pinfunction "4_C4") (pintype "bidirectional"))
    )
    (net (code "103") (name "Net-(IC6-A)") (class "Default")
      (node (ref "IC6") (pin "8") (pinfunction "A_8") (pintype "bidirectional"))
      (node (ref "J101") (pin "B5") (pinfunction "5_B5") (pintype "bidirectional"))
      (node (ref "R39") (pin "2") (pinfunction "P$2_2") (pintype "passive"))
    )
    (net (code "104") (name "Net-(IC6-B)") (class "Default")
      (node (ref "IC6") (pin "7") (pinfunction "B_7") (pintype "bidirectional"))
      (node (ref "J101") (pin "B2") (pinfunction "2_B2") (pintype "bidirectional"))
      (node (ref "R39") (pin "1") (pinfunction "P$1_1") (pintype "passive"))
    )
    (net (code "105") (name "Net-(IC6-Y)") (class "Default")
      (node (ref "IC6") (pin "5") (pinfunction "Y_5") (pintype "bidirectional"))
      (node (ref "J101") (pin "B3") (pinfunction "3_B3") (pintype "bidirectional"))
    )
    (net (code "106") (name "Net-(IC6-Z)") (class "Default")
      (node (ref "IC6") (pin "6") (pinfunction "Z_6") (pintype "bidirectional"))
      (node (ref "J101") (pin "B4") (pinfunction "4_B4") (pintype "bidirectional"))
    )
    (net (code "107") (name "Net-(IC7-A)") (class "Default")
      (node (ref "IC7") (pin "8") (pinfunction "A_8") (pintype "bidirectional"))
      (node (ref "J101") (pin "A5") (pinfunction "5_A5") (pintype "bidirectional"))
      (node (ref "R40") (pin "2") (pinfunction "P$2_2") (pintype "passive"))
    )
    (net (code "108") (name "Net-(IC7-B)") (class "Default")
      (node (ref "IC7") (pin "7") (pinfunction "B_7") (pintype "bidirectional"))
      (node (ref "J101") (pin "A2") (pinfunction "2_A2") (pintype "bidirectional"))
      (node (ref "R40") (pin "1") (pinfunction "P$1_1") (pintype "passive"))
    )
    (net (code "109") (name "Net-(IC7-Y)") (class "Default")
      (node (ref "IC7") (pin "5") (pinfunction "Y_5") (pintype "bidirectional"))
      (node (ref "J101") (pin "A3") (pinfunction "3_A3") (pintype "bidirectional"))
    )
    (net (code "110") (name "Net-(IC7-Z)") (class "Default")
      (node (ref "IC7") (pin "6") (pinfunction "Z_6") (pintype "bidirectional"))
      (node (ref "J101") (pin "A4") (pinfunction "4_A4") (pintype "bidirectional"))
    )
    (net (code "111") (name "Net-(J100-CENTER)") (class "Default")
      (node (ref "D11") (pin "A") (pinfunction "A_A") (pintype "bidirectional"))
      (node (ref "J100") (pin "1") (pinfunction "CENTER_1") (pintype "bidirectional"))
    )
    (net (code "112") (name "Net-(J101A-6)") (class "Default")
      (node (ref "D15") (pin "A") (pinfunction "A_A") (pintype "bidirectional"))
      (node (ref "J101") (pin "A6") (pinfunction "6_A6") (pintype "bidirectional"))
      (node (ref "LED6") (pin "A") (pinfunction "ANODE_A") (pintype "passive"))
    )
    (net (code "113") (name "Net-(J101B-6)") (class "Default")
      (node (ref "D14") (pin "A") (pinfunction "A_A") (pintype "bidirectional"))
      (node (ref "J101") (pin "B6") (pinfunction "6_B6") (pintype "bidirectional"))
      (node (ref "LED5") (pin "A") (pinfunction "ANODE_A") (pintype "passive"))
    )
    (net (code "114") (name "Net-(J101C-6)") (class "Default")
      (node (ref "D13") (pin "A") (pinfunction "A_A") (pintype "bidirectional"))
      (node (ref "J101") (pin "C6") (pinfunction "6_C6") (pintype "bidirectional"))
      (node (ref "LED4") (pin "A") (pinfunction "ANODE_A") (pintype "passive"))
    )
    (net (code "115") (name "Net-(J101D-6)") (class "Default")
      (node (ref "D12") (pin "A") (pinfunction "A_A") (pintype "bidirectional"))
      (node (ref "J101") (pin "D6") (pinfunction "6_D6") (pintype "bidirectional"))
      (node (ref "LED3") (pin "A") (pinfunction "ANODE_A") (pintype "passive"))
    )
    (net (code "116") (name "Net-(L10-P$1)") (class "Default")
      (node (ref "FUSE1") (pin "1") (pinfunction "1_1") (pintype "passive"))
      (node (ref "L10") (pin "1") (pinfunction "P$1_1") (pintype "passive"))
      (node (ref "L6") (pin "1") (pinfunction "P$1_1") (pintype "passive"))
      (node (ref "L7") (pin "1") (pinfunction "P$1_1") (pintype "passive"))
      (node (ref "L8") (pin "1") (pinfunction "P$1_1") (pintype "passive"))
      (node (ref "L9") (pin "1") (pinfunction "P$1_1") (pintype "passive"))
    )
    (net (code "117") (name "Net-(LED1-CATHODE)") (class "Default")
      (node (ref "LED1") (pin "C") (pinfunction "CATHODE_C") (pintype "passive"))
      (node (ref "R35") (pin "1") (pinfunction "P$1_1") (pintype "passive"))
    )
    (net (code "118") (name "Net-(LED2-CATHODE)") (class "Default")
      (node (ref "LED2") (pin "C") (pinfunction "CATHODE_C") (pintype "passive"))
      (node (ref "R36") (pin "1") (pinfunction "P$1_1") (pintype "passive"))
    )
    (net (code "119") (name "Net-(LED3-CATHODE)") (class "Default")
      (node (ref "LED3") (pin "C") (pinfunction "CATHODE_C") (pintype "passive"))
      (node (ref "R41") (pin "1") (pinfunction "P$1_1") (pintype "passive"))
    )
    (net (code "120") (name "Net-(LED4-CATHODE)") (class "Default")
      (node (ref "LED4") (pin "C") (pinfunction "CATHODE_C") (pintype "passive"))
      (node (ref "R42") (pin "1") (pinfunction "P$1_1") (pintype "passive"))
    )
    (net (code "121") (name "Net-(LED5-CATHODE)") (class "Default")
      (node (ref "LED5") (pin "C") (pinfunction "CATHODE_C") (pintype "passive"))
      (node (ref "R43") (pin "1") (pinfunction "P$1_1") (pintype "passive"))
    )
    (net (code "122") (name "Net-(LED6-CATHODE)") (class "Default")
      (node (ref "LED6") (pin "C") (pinfunction "CATHODE_C") (pintype "passive"))
      (node (ref "R44") (pin "1") (pinfunction "P$1_1") (pintype "passive"))
    )
    (net (code "123") (name "Net-(POWER-CATHODE)") (class "Default")
      (node (ref "POWER") (pin "C") (pinfunction "CATHODE_C") (pintype "passive"))
      (node (ref "R32") (pin "1") (pinfunction "P$1_1") (pintype "passive"))
    )
    (net (code "124") (name "Net-(POWER1-CATHODE)") (class "Default")
      (node (ref "POWER1") (pin "C") (pinfunction "CATHODE_C") (pintype "passive"))
      (node (ref "R33") (pin "1") (pinfunction "P$1_1") (pintype "passive"))
    )
    (net (code "125") (name "Net-(POWER2-CATHODE)") (class "Default")
      (node (ref "POWER2") (pin "C") (pinfunction "CATHODE_C") (pintype "passive"))
      (node (ref "R34") (pin "1") (pinfunction "P$1_1") (pintype "passive"))
    )
    (net (code "126") (name "Net-(Q2-D)") (class "Default")
      (node (ref "D2") (pin "A") (pinfunction "A_A") (pintype "bidirectional"))
      (node (ref "J3") (pin "2") (pinfunction "2_2") (pintype "bidirectional"))
      (node (ref "Q2") (pin "3") (pinfunction "D_3") (pintype "bidirectional"))
    )
    (net (code "127") (name "Net-(Q2-G)") (class "Default")
      (node (ref "Q2") (pin "1") (pinfunction "G_1") (pintype "bidirectional"))
      (node (ref "R16") (pin "2") (pinfunction "P$2_2") (pintype "passive"))
    )
    (net (code "128") (name "Net-(Q9-D)") (class "Default")
      (node (ref "D10") (pin "A") (pinfunction "A_A") (pintype "bidirectional"))
      (node (ref "J1") (pin "2") (pinfunction "2_2") (pintype "bidirectional"))
      (node (ref "Q9") (pin "3") (pinfunction "D_3") (pintype "bidirectional"))
    )
    (net (code "129") (name "Net-(Q9-G)") (class "Default")
      (node (ref "Q9") (pin "1") (pinfunction "G_1") (pintype "bidirectional"))
      (node (ref "R30") (pin "2") (pinfunction "P$2_2") (pintype "passive"))
    )
    (net (code "130") (name "Net-(R19-P$2)") (class "Default")
      (node (ref "J1") (pin "10") (pinfunction "10_10") (pintype "bidirectional"))
      (node (ref "R19") (pin "2") (pinfunction "P$2_2") (pintype "passive"))
    )
    (net (code "131") (name "Net-(R20-P$2)") (class "Default")
      (node (ref "J3") (pin "4") (pinfunction "4_4") (pintype "bidirectional"))
      (node (ref "R20") (pin "2") (pinfunction "P$2_2") (pintype "passive"))
    )
    (net (code "132") (name "Net-(R22-P$2)") (class "Default")
      (node (ref "J1") (pin "8") (pinfunction "8_8") (pintype "bidirectional"))
      (node (ref "R22") (pin "2") (pinfunction "P$2_2") (pintype "passive"))
    )
    (net (code "133") (name "Net-(R23-P$2)") (class "Default")
      (node (ref "J3") (pin "6") (pinfunction "6_6") (pintype "bidirectional"))
      (node (ref "R23") (pin "2") (pinfunction "P$2_2") (pintype "passive"))
    )
    (net (code "134") (name "Net-(R25-P$2)") (class "Default")
      (node (ref "J1") (pin "6") (pinfunction "6_6") (pintype "bidirectional"))
      (node (ref "R25") (pin "2") (pinfunction "P$2_2") (pintype "passive"))
    )
    (net (code "135") (name "Net-(R26-P$2)") (class "Default")
      (node (ref "J3") (pin "8") (pinfunction "8_8") (pintype "bidirectional"))
      (node (ref "R26") (pin "2") (pinfunction "P$2_2") (pintype "passive"))
    )
    (net (code "136") (name "Net-(R27-P$2)") (class "Default")
      (node (ref "J1") (pin "4") (pinfunction "4_4") (pintype "bidirectional"))
      (node (ref "R27") (pin "2") (pinfunction "P$2_2") (pintype "passive"))
    )
    (net (code "137") (name "Net-(R28-P$2)") (class "Default")
      (node (ref "J3") (pin "10") (pinfunction "10_10") (pintype "bidirectional"))
      (node (ref "R28") (pin "2") (pinfunction "P$2_2") (pintype "passive"))
    )
    (net (code "138") (name "P1L") (class "Default")
      (node (ref "IC1") (pin "44") (pinfunction "P1LED0_44") (pintype "bidirectional"))
      (node (ref "RN1") (pin "C1") (pinfunction "C1_C1") (pintype "passive"))
    )
    (net (code "139") (name "P1S") (class "Default")
      (node (ref "IC1") (pin "43") (pinfunction "P1LED1_43") (pintype "bidirectional"))
      (node (ref "RN1") (pin "D1") (pinfunction "D1_D1") (pintype "passive"))
    )
    (net (code "140") (name "P1_LINK") (class "Default")
      (node (ref "J102") (pin "GC") (pinfunction "GC_GC") (pintype "passive"))
      (node (ref "RN1") (pin "C2") (pinfunction "C2_C2") (pintype "passive"))
    )
    (net (code "141") (name "P1_SPEED") (class "Default")
      (node (ref "J102") (pin "YC") (pinfunction "YC_YC") (pintype "passive"))
      (node (ref "RN1") (pin "D2") (pinfunction "D2_D2") (pintype "passive"))
    )
    (net (code "142") (name "P2L") (class "Default")
      (node (ref "IC1") (pin "46") (pinfunction "P2LED0_46") (pintype "bidirectional"))
      (node (ref "RN1") (pin "A1") (pinfunction "A1_A1") (pintype "passive"))
    )
    (net (code "143") (name "P2S") (class "Default")
      (node (ref "IC1") (pin "45") (pinfunction "P2LED1_45") (pintype "bidirectional"))
      (node (ref "RN1") (pin "B1") (pinfunction "B1_B1") (pintype "passive"))
    )
    (net (code "144") (name "P2_LINK") (class "Default")
      (node (ref "J103") (pin "GC") (pinfunction "GC_GC") (pintype "passive"))
      (node (ref "RN1") (pin "A2") (pinfunction "A2_A2") (pintype "passive"))
    )
    (net (code "145") (name "P2_SPEED") (class "Default")
      (node (ref "J103") (pin "YC") (pinfunction "YC_YC") (pintype "passive"))
      (node (ref "RN1") (pin "B2") (pinfunction "B2_B2") (pintype "passive"))
    )
    (net (code "146") (name "RX2") (class "Default")
      (node (ref "IC2") (pin "87") (pinfunction "PD6_87") (pintype "bidirectional"))
      (node (ref "IC7") (pin "2") (pinfunction "RO_2") (pintype "bidirectional"))
    )
    (net (code "147") (name "RX4") (class "Default")
      (node (ref "IC2") (pin "79") (pinfunction "PC11_79") (pintype "bidirectional"))
      (node (ref "IC5") (pin "2") (pinfunction "RO_2") (pintype "bidirectional"))
    )
    (net (code "148") (name "RX5") (class "Default")
      (node (ref "IC2") (pin "83") (pinfunction "PD2_83") (pintype "bidirectional"))
      (node (ref "IC6") (pin "2") (pinfunction "RO_2") (pintype "bidirectional"))
    )
    (net (code "149") (name "RX6") (class "Default")
      (node (ref "IC2") (pin "64") (pinfunction "PC7_64") (pintype "bidirectional"))
      (node (ref "IC4") (pin "2") (pinfunction "RO_2") (pintype "bidirectional"))
    )
    (net (code "150") (name "SWCLK") (class "Default")
      (node (ref "IC2") (pin "76") (pinfunction "PA14_76") (pintype "bidirectional"))
      (node (ref "J4") (pin "2") (pinfunction "SWCLK_2") (pintype "bidirectional"))
    )
    (net (code "151") (name "SWDIO") (class "Default")
      (node (ref "IC2") (pin "72") (pinfunction "PA13_72") (pintype "bidirectional"))
      (node (ref "J4") (pin "4") (pinfunction "SWDIO_4") (pintype "bidirectional"))
    )
    (net (code "152") (name "TRACESWO") (class "Default")
      (node (ref "IC2") (pin "89") (pinfunction "PB3_89") (pintype "bidirectional"))
      (node (ref "J4") (pin "6") (pinfunction "TRACESWO_6") (pintype "bidirectional"))
    )
    (net (code "153") (name "TX2") (class "Default")
      (node (ref "IC2") (pin "86") (pinfunction "PD5_86") (pintype "bidirectional"))
      (node (ref "IC7") (pin "3") (pinfunction "DI_3") (pintype "bidirectional"))
    )
    (net (code "154") (name "TX4") (class "Default")
      (node (ref "IC2") (pin "78") (pinfunction "PC10_78") (pintype "bidirectional"))
      (node (ref "IC5") (pin "3") (pinfunction "DI_3") (pintype "bidirectional"))
    )
    (net (code "155") (name "TX5") (class "Default")
      (node (ref "IC2") (pin "80") (pinfunction "PC12_80") (pintype "bidirectional"))
      (node (ref "IC6") (pin "3") (pinfunction "DI_3") (pintype "bidirectional"))
    )
    (net (code "156") (name "TX6") (class "Default")
      (node (ref "IC2") (pin "63") (pinfunction "PC6_63") (pintype "bidirectional"))
      (node (ref "IC4") (pin "3") (pinfunction "DI_3") (pintype "bidirectional"))
    )
    (net (code "157") (name "unconnected-(IC1-SMTXER3{slash}MII_LINK_3-Pad24)") (class "Default")
      (node (ref "IC1") (pin "24") (pinfunction "SMTXER3/MII_LINK_3_24") (pintype "input"))
    )
    (net (code "158") (name "unconnected-(IC1-SPIQ-Pad38)") (class "Default")
      (node (ref "IC1") (pin "38") (pinfunction "SPIQ_38") (pintype "bidirectional"))
    )
    (net (code "159") (name "unconnected-(IC2A-PA4-Pad29)") (class "Default")
      (node (ref "IC2") (pin "29") (pinfunction "PA4_29") (pintype "bidirectional"))
    )
    (net (code "160") (name "unconnected-(IC2A-PA5-Pad30)") (class "Default")
      (node (ref "IC2") (pin "30") (pinfunction "PA5_30") (pintype "bidirectional"))
    )
    (net (code "161") (name "unconnected-(IC2A-PA6-Pad31)") (class "Default")
      (node (ref "IC2") (pin "31") (pinfunction "PA6_31") (pintype "bidirectional"))
    )
    (net (code "162") (name "unconnected-(IC2A-PA11-Pad70)") (class "Default")
      (node (ref "IC2") (pin "70") (pinfunction "PA11_70") (pintype "bidirectional"))
    )
    (net (code "163") (name "unconnected-(IC2A-PA12-Pad71)") (class "Default")
      (node (ref "IC2") (pin "71") (pinfunction "PA12_71") (pintype "bidirectional"))
    )
    (net (code "164") (name "unconnected-(IC2A-PA15-Pad77)") (class "Default")
      (node (ref "IC2") (pin "77") (pinfunction "PA15_77") (pintype "bidirectional"))
    )
    (net (code "165") (name "unconnected-(IC2B-PB2-Pad37)") (class "Default")
      (node (ref "IC2") (pin "37") (pinfunction "PB2_37") (pintype "bidirectional"))
    )
    (net (code "166") (name "unconnected-(IC2B-PB10-Pad47)") (class "Default")
      (node (ref "IC2") (pin "47") (pinfunction "PB10_47") (pintype "bidirectional"))
    )
    (net (code "167") (name "unconnected-(IC2B-PB14-Pad53)") (class "Default")
      (node (ref "IC2") (pin "53") (pinfunction "PB14_53") (pintype "bidirectional"))
    )
    (net (code "168") (name "unconnected-(IC2B-PB15-Pad54)") (class "Default")
      (node (ref "IC2") (pin "54") (pinfunction "PB15_54") (pintype "bidirectional"))
    )
    (net (code "169") (name "unconnected-(IC2C-PC0-Pad15)") (class "Default")
      (node (ref "IC2") (pin "15") (pinfunction "PC0_15") (pintype "bidirectional"))
    )
    (net (code "170") (name "unconnected-(IC2C-PC14-Pad8)") (class "Default")
      (node (ref "IC2") (pin "8") (pinfunction "PC14_8") (pintype "bidirectional"))
    )
    (net (code "171") (name "unconnected-(IC2C-PC15-Pad9)") (class "Default")
      (node (ref "IC2") (pin "9") (pinfunction "PC15_9") (pintype "bidirectional"))
    )
    (net (code "172") (name "unconnected-(IC2D-PD0-Pad81)") (class "Default")
      (node (ref "IC2") (pin "81") (pinfunction "PD0_81") (pintype "bidirectional"))
    )
    (net (code "173") (name "unconnected-(IC2D-PD1-Pad82)") (class "Default")
      (node (ref "IC2") (pin "82") (pinfunction "PD1_82") (pintype "bidirectional"))
    )
    (net (code "174") (name "unconnected-(IC2D-PD3-Pad84)") (class "Default")
      (node (ref "IC2") (pin "84") (pinfunction "PD3_84") (pintype "bidirectional"))
    )
    (net (code "175") (name "unconnected-(IC2D-PD4-Pad85)") (class "Default")
      (node (ref "IC2") (pin "85") (pinfunction "PD4_85") (pintype "bidirectional"))
    )
    (net (code "176") (name "unconnected-(IC2E-PE15-Pad46)") (class "Default")
      (node (ref "IC2") (pin "46") (pinfunction "PE15_46") (pintype "bidirectional"))
    )
    (net (code "177") (name "unconnected-(J100-SLV_SHNT-Pad3)") (class "Default")
      (node (ref "J100") (pin "3") (pinfunction "SLV_SHNT_3") (pintype "bidirectional"))
    )
    (net (code "178") (name "~{RST}") (class "Default")
      (node (ref "IC2") (pin "14") (pinfunction "NRST_14") (pintype "bidirectional"))
      (node (ref "J4") (pin "5") (pinfunction "RESET_5") (pintype "bidirectional"))
    )
  )
)
